# Adapters.net
KiCad netlist of a schematic drawn in Altium Designer
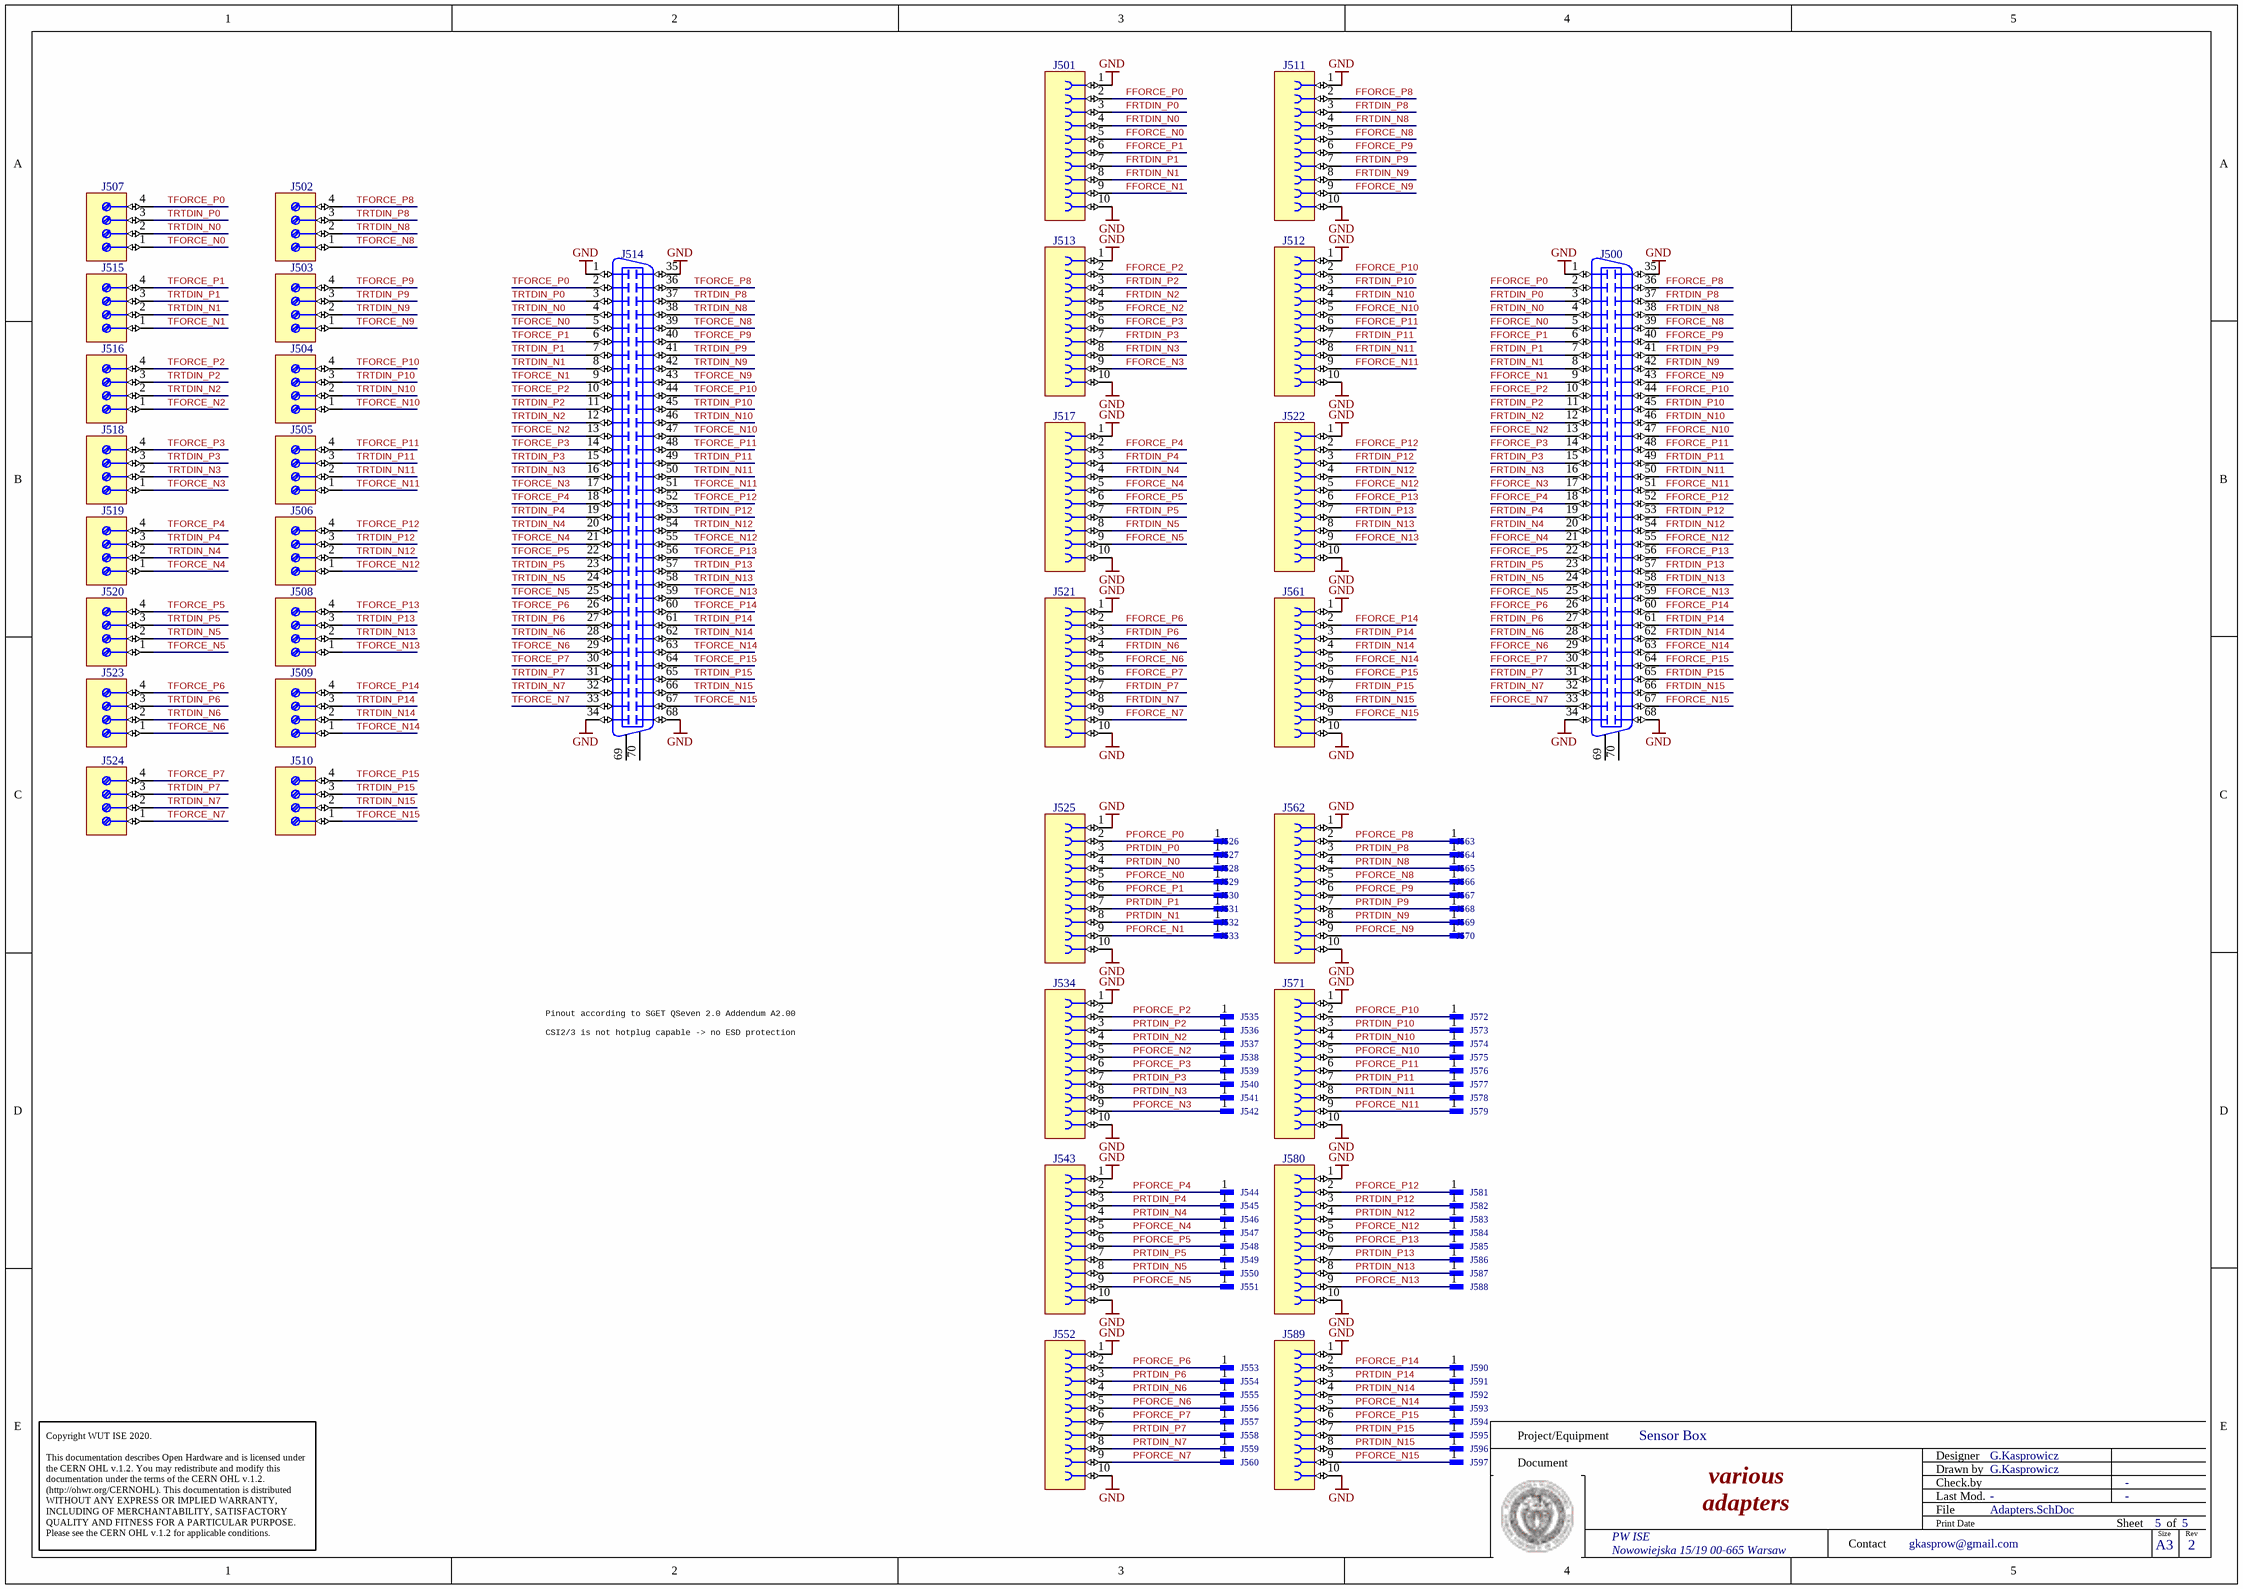
[diagram p0: Adapters.SchDoc]

(export (version "E")
  (design (tool "Eeschema 10.0.6"))
  (components
    (comp (ref "J500")
      (value "DNP")
      (footprint "MOLEX_71430-0013")
      (description "Very High Density Cable Interconnect (VHDCI ) 68 Female")
      (fields
        (field (name "PART NUMBER") "MOLEX_71430-0013")
        (field (name "MANUFACTURER") "MOLEX")
        (field (name "AUTHOR") "CERN DEM JLC")
      )
      (libsource (lib "FMC_DIO_32ch_lvds_a") (part "MOLEX_71430-0013"))
    )
    (comp (ref "J501")
      (value "FFC/FPC")
      (footprint "MOLEX_52745-1097")
      (description "Connector 10 Female")
      (fields
        (field (name "PART NUMBER") "MOLEX_52745-1097")
        (field (name "MANUFACTURER") "MOLEX")
        (field (name "AUTHOR") "CERN DEM JLC")
      )
      (libsource (lib "Connectors") (part "Connector 10 Female"))
    )
    (comp (ref "J502")
      (value "~")
      (footprint "PHOENIX_1725672")
      (description "Terminal Block, 4 Positions, Screw Connection")
      (fields
        (field (name "PART NUMBER") "PHOENIX_1725672")
        (field (name "MANUFACTURER") "PHOENIX CONTACT")
        (field (name "AUTHOR") "CERN DEM JMW")
      )
      (libsource (lib "Connectors") (part "Terminal Block_4 Positions_Screw Connection"))
    )
    (comp (ref "J503")
      (value "~")
      (footprint "PHOENIX_1725672")
      (description "Terminal Block, 4 Positions, Screw Connection")
      (fields
        (field (name "PART NUMBER") "PHOENIX_1725672")
        (field (name "MANUFACTURER") "PHOENIX CONTACT")
        (field (name "AUTHOR") "CERN DEM JMW")
      )
      (libsource (lib "Connectors") (part "Terminal Block_4 Positions_Screw Connection"))
    )
    (comp (ref "J504")
      (value "~")
      (footprint "PHOENIX_1725672")
      (description "Terminal Block, 4 Positions, Screw Connection")
      (fields
        (field (name "PART NUMBER") "PHOENIX_1725672")
        (field (name "MANUFACTURER") "PHOENIX CONTACT")
        (field (name "AUTHOR") "CERN DEM JMW")
      )
      (libsource (lib "Connectors") (part "Terminal Block_4 Positions_Screw Connection"))
    )
    (comp (ref "J505")
      (value "~")
      (footprint "PHOENIX_1725672")
      (description "Terminal Block, 4 Positions, Screw Connection")
      (fields
        (field (name "PART NUMBER") "PHOENIX_1725672")
        (field (name "MANUFACTURER") "PHOENIX CONTACT")
        (field (name "AUTHOR") "CERN DEM JMW")
      )
      (libsource (lib "Connectors") (part "Terminal Block_4 Positions_Screw Connection"))
    )
    (comp (ref "J506")
      (value "~")
      (footprint "PHOENIX_1725672")
      (description "Terminal Block, 4 Positions, Screw Connection")
      (fields
        (field (name "PART NUMBER") "PHOENIX_1725672")
        (field (name "MANUFACTURER") "PHOENIX CONTACT")
        (field (name "AUTHOR") "CERN DEM JMW")
      )
      (libsource (lib "Connectors") (part "Terminal Block_4 Positions_Screw Connection"))
    )
    (comp (ref "J507")
      (value "~")
      (footprint "PHOENIX_1725672")
      (description "Terminal Block, 4 Positions, Screw Connection")
      (fields
        (field (name "PART NUMBER") "PHOENIX_1725672")
        (field (name "MANUFACTURER") "PHOENIX CONTACT")
        (field (name "AUTHOR") "CERN DEM JMW")
      )
      (libsource (lib "Connectors") (part "Terminal Block_4 Positions_Screw Connection"))
    )
    (comp (ref "J508")
      (value "~")
      (footprint "PHOENIX_1725672")
      (description "Terminal Block, 4 Positions, Screw Connection")
      (fields
        (field (name "PART NUMBER") "PHOENIX_1725672")
        (field (name "MANUFACTURER") "PHOENIX CONTACT")
        (field (name "AUTHOR") "CERN DEM JMW")
      )
      (libsource (lib "Connectors") (part "Terminal Block_4 Positions_Screw Connection"))
    )
    (comp (ref "J509")
      (value "~")
      (footprint "PHOENIX_1725672")
      (description "Terminal Block, 4 Positions, Screw Connection")
      (fields
        (field (name "PART NUMBER") "PHOENIX_1725672")
        (field (name "MANUFACTURER") "PHOENIX CONTACT")
        (field (name "AUTHOR") "CERN DEM JMW")
      )
      (libsource (lib "Connectors") (part "Terminal Block_4 Positions_Screw Connection"))
    )
    (comp (ref "J510")
      (value "~")
      (footprint "PHOENIX_1725672")
      (description "Terminal Block, 4 Positions, Screw Connection")
      (fields
        (field (name "PART NUMBER") "PHOENIX_1725672")
        (field (name "MANUFACTURER") "PHOENIX CONTACT")
        (field (name "AUTHOR") "CERN DEM JMW")
      )
      (libsource (lib "Connectors") (part "Terminal Block_4 Positions_Screw Connection"))
    )
    (comp (ref "J511")
      (value "FFC/FPC")
      (footprint "MOLEX_52745-1097")
      (description "Connector 10 Female")
      (fields
        (field (name "PART NUMBER") "MOLEX_52745-1097")
        (field (name "MANUFACTURER") "MOLEX")
        (field (name "AUTHOR") "CERN DEM JLC")
      )
      (libsource (lib "Connectors") (part "Connector 10 Female"))
    )
    (comp (ref "J512")
      (value "FFC/FPC")
      (footprint "MOLEX_52745-1097")
      (description "Connector 10 Female")
      (fields
        (field (name "PART NUMBER") "MOLEX_52745-1097")
        (field (name "MANUFACTURER") "MOLEX")
        (field (name "AUTHOR") "CERN DEM JLC")
      )
      (libsource (lib "Connectors") (part "Connector 10 Female"))
    )
    (comp (ref "J513")
      (value "FFC/FPC")
      (footprint "MOLEX_52745-1097")
      (description "Connector 10 Female")
      (fields
        (field (name "PART NUMBER") "MOLEX_52745-1097")
        (field (name "MANUFACTURER") "MOLEX")
        (field (name "AUTHOR") "CERN DEM JLC")
      )
      (libsource (lib "Connectors") (part "Connector 10 Female"))
    )
    (comp (ref "J514")
      (value "DNP")
      (footprint "MOLEX_71430-0013")
      (description "Very High Density Cable Interconnect (VHDCI ) 68 Female")
      (fields
        (field (name "PART NUMBER") "MOLEX_71430-0013")
        (field (name "MANUFACTURER") "MOLEX")
        (field (name "AUTHOR") "CERN DEM JLC")
      )
      (libsource (lib "FMC_DIO_32ch_lvds_a") (part "MOLEX_71430-0013"))
    )
    (comp (ref "J515")
      (value "~")
      (footprint "PHOENIX_1725672")
      (description "Terminal Block, 4 Positions, Screw Connection")
      (fields
        (field (name "PART NUMBER") "PHOENIX_1725672")
        (field (name "MANUFACTURER") "PHOENIX CONTACT")
        (field (name "AUTHOR") "CERN DEM JMW")
      )
      (libsource (lib "Connectors") (part "Terminal Block_4 Positions_Screw Connection"))
    )
    (comp (ref "J516")
      (value "~")
      (footprint "PHOENIX_1725672")
      (description "Terminal Block, 4 Positions, Screw Connection")
      (fields
        (field (name "PART NUMBER") "PHOENIX_1725672")
        (field (name "MANUFACTURER") "PHOENIX CONTACT")
        (field (name "AUTHOR") "CERN DEM JMW")
      )
      (libsource (lib "Connectors") (part "Terminal Block_4 Positions_Screw Connection"))
    )
    (comp (ref "J517")
      (value "FFC/FPC")
      (footprint "MOLEX_52745-1097")
      (description "Connector 10 Female")
      (fields
        (field (name "PART NUMBER") "MOLEX_52745-1097")
        (field (name "MANUFACTURER") "MOLEX")
        (field (name "AUTHOR") "CERN DEM JLC")
      )
      (libsource (lib "Connectors") (part "Connector 10 Female"))
    )
    (comp (ref "J518")
      (value "~")
      (footprint "PHOENIX_1725672")
      (description "Terminal Block, 4 Positions, Screw Connection")
      (fields
        (field (name "PART NUMBER") "PHOENIX_1725672")
        (field (name "MANUFACTURER") "PHOENIX CONTACT")
        (field (name "AUTHOR") "CERN DEM JMW")
      )
      (libsource (lib "Connectors") (part "Terminal Block_4 Positions_Screw Connection"))
    )
    (comp (ref "J519")
      (value "~")
      (footprint "PHOENIX_1725672")
      (description "Terminal Block, 4 Positions, Screw Connection")
      (fields
        (field (name "PART NUMBER") "PHOENIX_1725672")
        (field (name "MANUFACTURER") "PHOENIX CONTACT")
        (field (name "AUTHOR") "CERN DEM JMW")
      )
      (libsource (lib "Connectors") (part "Terminal Block_4 Positions_Screw Connection"))
    )
    (comp (ref "J520")
      (value "~")
      (footprint "PHOENIX_1725672")
      (description "Terminal Block, 4 Positions, Screw Connection")
      (fields
        (field (name "PART NUMBER") "PHOENIX_1725672")
        (field (name "MANUFACTURER") "PHOENIX CONTACT")
        (field (name "AUTHOR") "CERN DEM JMW")
      )
      (libsource (lib "Connectors") (part "Terminal Block_4 Positions_Screw Connection"))
    )
    (comp (ref "J521")
      (value "FFC/FPC")
      (footprint "MOLEX_52745-1097")
      (description "Connector 10 Female")
      (fields
        (field (name "PART NUMBER") "MOLEX_52745-1097")
        (field (name "MANUFACTURER") "MOLEX")
        (field (name "AUTHOR") "CERN DEM JLC")
      )
      (libsource (lib "Connectors") (part "Connector 10 Female"))
    )
    (comp (ref "J522")
      (value "FFC/FPC")
      (footprint "MOLEX_52745-1097")
      (description "Connector 10 Female")
      (fields
        (field (name "PART NUMBER") "MOLEX_52745-1097")
        (field (name "MANUFACTURER") "MOLEX")
        (field (name "AUTHOR") "CERN DEM JLC")
      )
      (libsource (lib "Connectors") (part "Connector 10 Female"))
    )
    (comp (ref "J523")
      (value "~")
      (footprint "PHOENIX_1725672")
      (description "Terminal Block, 4 Positions, Screw Connection")
      (fields
        (field (name "PART NUMBER") "PHOENIX_1725672")
        (field (name "MANUFACTURER") "PHOENIX CONTACT")
        (field (name "AUTHOR") "CERN DEM JMW")
      )
      (libsource (lib "Connectors") (part "Terminal Block_4 Positions_Screw Connection"))
    )
    (comp (ref "J524")
      (value "~")
      (footprint "PHOENIX_1725672")
      (description "Terminal Block, 4 Positions, Screw Connection")
      (fields
        (field (name "PART NUMBER") "PHOENIX_1725672")
        (field (name "MANUFACTURER") "PHOENIX CONTACT")
        (field (name "AUTHOR") "CERN DEM JMW")
      )
      (libsource (lib "Connectors") (part "Terminal Block_4 Positions_Screw Connection"))
    )
    (comp (ref "J525")
      (value "FFC/FPC")
      (footprint "MOLEX_52745-1097")
      (description "Connector 10 Female")
      (fields
        (field (name "PART NUMBER") "MOLEX_52745-1097")
        (field (name "MANUFACTURER") "MOLEX")
        (field (name "AUTHOR") "CERN DEM JLC")
      )
      (libsource (lib "Connectors") (part "Connector 10 Female"))
    )
    (comp (ref "J526")
      (value "SMD Pad")
      (footprint "R350X200")
      (description "Single SMD Pad")
      (fields (field (name "PART NUMBER") "SMD_PAD_3.5X2MM") (field (name "AUTHOR") "CERN DEM JLC"))
      (libsource (lib "Eletro-mechanical") (part "Single SMD Pad"))
    )
    (comp (ref "J527")
      (value "SMD Pad")
      (footprint "R350X200")
      (description "Single SMD Pad")
      (fields (field (name "PART NUMBER") "SMD_PAD_3.5X2MM") (field (name "AUTHOR") "CERN DEM JLC"))
      (libsource (lib "Eletro-mechanical") (part "Single SMD Pad"))
    )
    (comp (ref "J528")
      (value "SMD Pad")
      (footprint "R350X200")
      (description "Single SMD Pad")
      (fields (field (name "PART NUMBER") "SMD_PAD_3.5X2MM") (field (name "AUTHOR") "CERN DEM JLC"))
      (libsource (lib "Eletro-mechanical") (part "Single SMD Pad"))
    )
    (comp (ref "J529")
      (value "SMD Pad")
      (footprint "R350X200")
      (description "Single SMD Pad")
      (fields (field (name "PART NUMBER") "SMD_PAD_3.5X2MM") (field (name "AUTHOR") "CERN DEM JLC"))
      (libsource (lib "Eletro-mechanical") (part "Single SMD Pad"))
    )
    (comp (ref "J530")
      (value "SMD Pad")
      (footprint "R350X200")
      (description "Single SMD Pad")
      (fields (field (name "PART NUMBER") "SMD_PAD_3.5X2MM") (field (name "AUTHOR") "CERN DEM JLC"))
      (libsource (lib "Eletro-mechanical") (part "Single SMD Pad"))
    )
    (comp (ref "J531")
      (value "SMD Pad")
      (footprint "R350X200")
      (description "Single SMD Pad")
      (fields (field (name "PART NUMBER") "SMD_PAD_3.5X2MM") (field (name "AUTHOR") "CERN DEM JLC"))
      (libsource (lib "Eletro-mechanical") (part "Single SMD Pad"))
    )
    (comp (ref "J532")
      (value "SMD Pad")
      (footprint "R350X200")
      (description "Single SMD Pad")
      (fields (field (name "PART NUMBER") "SMD_PAD_3.5X2MM") (field (name "AUTHOR") "CERN DEM JLC"))
      (libsource (lib "Eletro-mechanical") (part "Single SMD Pad"))
    )
    (comp (ref "J533")
      (value "SMD Pad")
      (footprint "R350X200")
      (description "Single SMD Pad")
      (fields (field (name "PART NUMBER") "SMD_PAD_3.5X2MM") (field (name "AUTHOR") "CERN DEM JLC"))
      (libsource (lib "Eletro-mechanical") (part "Single SMD Pad"))
    )
    (comp (ref "J534")
      (value "FFC/FPC")
      (footprint "MOLEX_52745-1097")
      (description "Connector 10 Female")
      (fields
        (field (name "PART NUMBER") "MOLEX_52745-1097")
        (field (name "MANUFACTURER") "MOLEX")
        (field (name "AUTHOR") "CERN DEM JLC")
      )
      (libsource (lib "Connectors") (part "Connector 10 Female"))
    )
    (comp (ref "J535")
      (value "SMD Pad")
      (footprint "R350X200")
      (description "Single SMD Pad")
      (fields (field (name "PART NUMBER") "SMD_PAD_3.5X2MM") (field (name "AUTHOR") "CERN DEM JLC"))
      (libsource (lib "Eletro-mechanical") (part "Single SMD Pad"))
    )
    (comp (ref "J536")
      (value "SMD Pad")
      (footprint "R350X200")
      (description "Single SMD Pad")
      (fields (field (name "PART NUMBER") "SMD_PAD_3.5X2MM") (field (name "AUTHOR") "CERN DEM JLC"))
      (libsource (lib "Eletro-mechanical") (part "Single SMD Pad"))
    )
    (comp (ref "J537")
      (value "SMD Pad")
      (footprint "R350X200")
      (description "Single SMD Pad")
      (fields (field (name "PART NUMBER") "SMD_PAD_3.5X2MM") (field (name "AUTHOR") "CERN DEM JLC"))
      (libsource (lib "Eletro-mechanical") (part "Single SMD Pad"))
    )
    (comp (ref "J538")
      (value "SMD Pad")
      (footprint "R350X200")
      (description "Single SMD Pad")
      (fields (field (name "PART NUMBER") "SMD_PAD_3.5X2MM") (field (name "AUTHOR") "CERN DEM JLC"))
      (libsource (lib "Eletro-mechanical") (part "Single SMD Pad"))
    )
    (comp (ref "J539")
      (value "SMD Pad")
      (footprint "R350X200")
      (description "Single SMD Pad")
      (fields (field (name "PART NUMBER") "SMD_PAD_3.5X2MM") (field (name "AUTHOR") "CERN DEM JLC"))
      (libsource (lib "Eletro-mechanical") (part "Single SMD Pad"))
    )
    (comp (ref "J540")
      (value "SMD Pad")
      (footprint "R350X200")
      (description "Single SMD Pad")
      (fields (field (name "PART NUMBER") "SMD_PAD_3.5X2MM") (field (name "AUTHOR") "CERN DEM JLC"))
      (libsource (lib "Eletro-mechanical") (part "Single SMD Pad"))
    )
    (comp (ref "J541")
      (value "SMD Pad")
      (footprint "R350X200")
      (description "Single SMD Pad")
      (fields (field (name "PART NUMBER") "SMD_PAD_3.5X2MM") (field (name "AUTHOR") "CERN DEM JLC"))
      (libsource (lib "Eletro-mechanical") (part "Single SMD Pad"))
    )
    (comp (ref "J542")
      (value "SMD Pad")
      (footprint "R350X200")
      (description "Single SMD Pad")
      (fields (field (name "PART NUMBER") "SMD_PAD_3.5X2MM") (field (name "AUTHOR") "CERN DEM JLC"))
      (libsource (lib "Eletro-mechanical") (part "Single SMD Pad"))
    )
    (comp (ref "J543")
      (value "FFC/FPC")
      (footprint "MOLEX_52745-1097")
      (description "Connector 10 Female")
      (fields
        (field (name "PART NUMBER") "MOLEX_52745-1097")
        (field (name "MANUFACTURER") "MOLEX")
        (field (name "AUTHOR") "CERN DEM JLC")
      )
      (libsource (lib "Connectors") (part "Connector 10 Female"))
    )
    (comp (ref "J544")
      (value "SMD Pad")
      (footprint "R350X200")
      (description "Single SMD Pad")
      (fields (field (name "PART NUMBER") "SMD_PAD_3.5X2MM") (field (name "AUTHOR") "CERN DEM JLC"))
      (libsource (lib "Eletro-mechanical") (part "Single SMD Pad"))
    )
    (comp (ref "J545")
      (value "SMD Pad")
      (footprint "R350X200")
      (description "Single SMD Pad")
      (fields (field (name "PART NUMBER") "SMD_PAD_3.5X2MM") (field (name "AUTHOR") "CERN DEM JLC"))
      (libsource (lib "Eletro-mechanical") (part "Single SMD Pad"))
    )
    (comp (ref "J546")
      (value "SMD Pad")
      (footprint "R350X200")
      (description "Single SMD Pad")
      (fields (field (name "PART NUMBER") "SMD_PAD_3.5X2MM") (field (name "AUTHOR") "CERN DEM JLC"))
      (libsource (lib "Eletro-mechanical") (part "Single SMD Pad"))
    )
    (comp (ref "J547")
      (value "SMD Pad")
      (footprint "R350X200")
      (description "Single SMD Pad")
      (fields (field (name "PART NUMBER") "SMD_PAD_3.5X2MM") (field (name "AUTHOR") "CERN DEM JLC"))
      (libsource (lib "Eletro-mechanical") (part "Single SMD Pad"))
    )
    (comp (ref "J548")
      (value "SMD Pad")
      (footprint "R350X200")
      (description "Single SMD Pad")
      (fields (field (name "PART NUMBER") "SMD_PAD_3.5X2MM") (field (name "AUTHOR") "CERN DEM JLC"))
      (libsource (lib "Eletro-mechanical") (part "Single SMD Pad"))
    )
    (comp (ref "J549")
      (value "SMD Pad")
      (footprint "R350X200")
      (description "Single SMD Pad")
      (fields (field (name "PART NUMBER") "SMD_PAD_3.5X2MM") (field (name "AUTHOR") "CERN DEM JLC"))
      (libsource (lib "Eletro-mechanical") (part "Single SMD Pad"))
    )
    (comp (ref "J550")
      (value "SMD Pad")
      (footprint "R350X200")
      (description "Single SMD Pad")
      (fields (field (name "PART NUMBER") "SMD_PAD_3.5X2MM") (field (name "AUTHOR") "CERN DEM JLC"))
      (libsource (lib "Eletro-mechanical") (part "Single SMD Pad"))
    )
    (comp (ref "J551")
      (value "SMD Pad")
      (footprint "R350X200")
      (description "Single SMD Pad")
      (fields (field (name "PART NUMBER") "SMD_PAD_3.5X2MM") (field (name "AUTHOR") "CERN DEM JLC"))
      (libsource (lib "Eletro-mechanical") (part "Single SMD Pad"))
    )
    (comp (ref "J552")
      (value "FFC/FPC")
      (footprint "MOLEX_52745-1097")
      (description "Connector 10 Female")
      (fields
        (field (name "PART NUMBER") "MOLEX_52745-1097")
        (field (name "MANUFACTURER") "MOLEX")
        (field (name "AUTHOR") "CERN DEM JLC")
      )
      (libsource (lib "Connectors") (part "Connector 10 Female"))
    )
    (comp (ref "J553")
      (value "SMD Pad")
      (footprint "R350X200")
      (description "Single SMD Pad")
      (fields (field (name "PART NUMBER") "SMD_PAD_3.5X2MM") (field (name "AUTHOR") "CERN DEM JLC"))
      (libsource (lib "Eletro-mechanical") (part "Single SMD Pad"))
    )
    (comp (ref "J554")
      (value "SMD Pad")
      (footprint "R350X200")
      (description "Single SMD Pad")
      (fields (field (name "PART NUMBER") "SMD_PAD_3.5X2MM") (field (name "AUTHOR") "CERN DEM JLC"))
      (libsource (lib "Eletro-mechanical") (part "Single SMD Pad"))
    )
    (comp (ref "J555")
      (value "SMD Pad")
      (footprint "R350X200")
      (description "Single SMD Pad")
      (fields (field (name "PART NUMBER") "SMD_PAD_3.5X2MM") (field (name "AUTHOR") "CERN DEM JLC"))
      (libsource (lib "Eletro-mechanical") (part "Single SMD Pad"))
    )
    (comp (ref "J556")
      (value "SMD Pad")
      (footprint "R350X200")
      (description "Single SMD Pad")
      (fields (field (name "PART NUMBER") "SMD_PAD_3.5X2MM") (field (name "AUTHOR") "CERN DEM JLC"))
      (libsource (lib "Eletro-mechanical") (part "Single SMD Pad"))
    )
    (comp (ref "J557")
      (value "SMD Pad")
      (footprint "R350X200")
      (description "Single SMD Pad")
      (fields (field (name "PART NUMBER") "SMD_PAD_3.5X2MM") (field (name "AUTHOR") "CERN DEM JLC"))
      (libsource (lib "Eletro-mechanical") (part "Single SMD Pad"))
    )
    (comp (ref "J558")
      (value "SMD Pad")
      (footprint "R350X200")
      (description "Single SMD Pad")
      (fields (field (name "PART NUMBER") "SMD_PAD_3.5X2MM") (field (name "AUTHOR") "CERN DEM JLC"))
      (libsource (lib "Eletro-mechanical") (part "Single SMD Pad"))
    )
    (comp (ref "J559")
      (value "SMD Pad")
      (footprint "R350X200")
      (description "Single SMD Pad")
      (fields (field (name "PART NUMBER") "SMD_PAD_3.5X2MM") (field (name "AUTHOR") "CERN DEM JLC"))
      (libsource (lib "Eletro-mechanical") (part "Single SMD Pad"))
    )
    (comp (ref "J560")
      (value "SMD Pad")
      (footprint "R350X200")
      (description "Single SMD Pad")
      (fields (field (name "PART NUMBER") "SMD_PAD_3.5X2MM") (field (name "AUTHOR") "CERN DEM JLC"))
      (libsource (lib "Eletro-mechanical") (part "Single SMD Pad"))
    )
    (comp (ref "J561")
      (value "FFC/FPC")
      (footprint "MOLEX_52745-1097")
      (description "Connector 10 Female")
      (fields
        (field (name "PART NUMBER") "MOLEX_52745-1097")
        (field (name "MANUFACTURER") "MOLEX")
        (field (name "AUTHOR") "CERN DEM JLC")
      )
      (libsource (lib "Connectors") (part "Connector 10 Female"))
    )
    (comp (ref "J562")
      (value "FFC/FPC")
      (footprint "MOLEX_52745-1097")
      (description "Connector 10 Female")
      (fields
        (field (name "PART NUMBER") "MOLEX_52745-1097")
        (field (name "MANUFACTURER") "MOLEX")
        (field (name "AUTHOR") "CERN DEM JLC")
      )
      (libsource (lib "Connectors") (part "Connector 10 Female"))
    )
    (comp (ref "J563")
      (value "SMD Pad")
      (footprint "R350X200")
      (description "Single SMD Pad")
      (fields (field (name "PART NUMBER") "SMD_PAD_3.5X2MM") (field (name "AUTHOR") "CERN DEM JLC"))
      (libsource (lib "Eletro-mechanical") (part "Single SMD Pad"))
    )
    (comp (ref "J564")
      (value "SMD Pad")
      (footprint "R350X200")
      (description "Single SMD Pad")
      (fields (field (name "PART NUMBER") "SMD_PAD_3.5X2MM") (field (name "AUTHOR") "CERN DEM JLC"))
      (libsource (lib "Eletro-mechanical") (part "Single SMD Pad"))
    )
    (comp (ref "J565")
      (value "SMD Pad")
      (footprint "R350X200")
      (description "Single SMD Pad")
      (fields (field (name "PART NUMBER") "SMD_PAD_3.5X2MM") (field (name "AUTHOR") "CERN DEM JLC"))
      (libsource (lib "Eletro-mechanical") (part "Single SMD Pad"))
    )
    (comp (ref "J566")
      (value "SMD Pad")
      (footprint "R350X200")
      (description "Single SMD Pad")
      (fields (field (name "PART NUMBER") "SMD_PAD_3.5X2MM") (field (name "AUTHOR") "CERN DEM JLC"))
      (libsource (lib "Eletro-mechanical") (part "Single SMD Pad"))
    )
    (comp (ref "J567")
      (value "SMD Pad")
      (footprint "R350X200")
      (description "Single SMD Pad")
      (fields (field (name "PART NUMBER") "SMD_PAD_3.5X2MM") (field (name "AUTHOR") "CERN DEM JLC"))
      (libsource (lib "Eletro-mechanical") (part "Single SMD Pad"))
    )
    (comp (ref "J568")
      (value "SMD Pad")
      (footprint "R350X200")
      (description "Single SMD Pad")
      (fields (field (name "PART NUMBER") "SMD_PAD_3.5X2MM") (field (name "AUTHOR") "CERN DEM JLC"))
      (libsource (lib "Eletro-mechanical") (part "Single SMD Pad"))
    )
    (comp (ref "J569")
      (value "SMD Pad")
      (footprint "R350X200")
      (description "Single SMD Pad")
      (fields (field (name "PART NUMBER") "SMD_PAD_3.5X2MM") (field (name "AUTHOR") "CERN DEM JLC"))
      (libsource (lib "Eletro-mechanical") (part "Single SMD Pad"))
    )
    (comp (ref "J570")
      (value "SMD Pad")
      (footprint "R350X200")
      (description "Single SMD Pad")
      (fields (field (name "PART NUMBER") "SMD_PAD_3.5X2MM") (field (name "AUTHOR") "CERN DEM JLC"))
      (libsource (lib "Eletro-mechanical") (part "Single SMD Pad"))
    )
    (comp (ref "J571")
      (value "FFC/FPC")
      (footprint "MOLEX_52745-1097")
      (description "Connector 10 Female")
      (fields
        (field (name "PART NUMBER") "MOLEX_52745-1097")
        (field (name "MANUFACTURER") "MOLEX")
        (field (name "AUTHOR") "CERN DEM JLC")
      )
      (libsource (lib "Connectors") (part "Connector 10 Female"))
    )
    (comp (ref "J572")
      (value "SMD Pad")
      (footprint "R350X200")
      (description "Single SMD Pad")
      (fields (field (name "PART NUMBER") "SMD_PAD_3.5X2MM") (field (name "AUTHOR") "CERN DEM JLC"))
      (libsource (lib "Eletro-mechanical") (part "Single SMD Pad"))
    )
    (comp (ref "J573")
      (value "SMD Pad")
      (footprint "R350X200")
      (description "Single SMD Pad")
      (fields (field (name "PART NUMBER") "SMD_PAD_3.5X2MM") (field (name "AUTHOR") "CERN DEM JLC"))
      (libsource (lib "Eletro-mechanical") (part "Single SMD Pad"))
    )
    (comp (ref "J574")
      (value "SMD Pad")
      (footprint "R350X200")
      (description "Single SMD Pad")
      (fields (field (name "PART NUMBER") "SMD_PAD_3.5X2MM") (field (name "AUTHOR") "CERN DEM JLC"))
      (libsource (lib "Eletro-mechanical") (part "Single SMD Pad"))
    )
    (comp (ref "J575")
      (value "SMD Pad")
      (footprint "R350X200")
      (description "Single SMD Pad")
      (fields (field (name "PART NUMBER") "SMD_PAD_3.5X2MM") (field (name "AUTHOR") "CERN DEM JLC"))
      (libsource (lib "Eletro-mechanical") (part "Single SMD Pad"))
    )
    (comp (ref "J576")
      (value "SMD Pad")
      (footprint "R350X200")
      (description "Single SMD Pad")
      (fields (field (name "PART NUMBER") "SMD_PAD_3.5X2MM") (field (name "AUTHOR") "CERN DEM JLC"))
      (libsource (lib "Eletro-mechanical") (part "Single SMD Pad"))
    )
    (comp (ref "J577")
      (value "SMD Pad")
      (footprint "R350X200")
      (description "Single SMD Pad")
      (fields (field (name "PART NUMBER") "SMD_PAD_3.5X2MM") (field (name "AUTHOR") "CERN DEM JLC"))
      (libsource (lib "Eletro-mechanical") (part "Single SMD Pad"))
    )
    (comp (ref "J578")
      (value "SMD Pad")
      (footprint "R350X200")
      (description "Single SMD Pad")
      (fields (field (name "PART NUMBER") "SMD_PAD_3.5X2MM") (field (name "AUTHOR") "CERN DEM JLC"))
      (libsource (lib "Eletro-mechanical") (part "Single SMD Pad"))
    )
    (comp (ref "J579")
      (value "SMD Pad")
      (footprint "R350X200")
      (description "Single SMD Pad")
      (fields (field (name "PART NUMBER") "SMD_PAD_3.5X2MM") (field (name "AUTHOR") "CERN DEM JLC"))
      (libsource (lib "Eletro-mechanical") (part "Single SMD Pad"))
    )
    (comp (ref "J580")
      (value "FFC/FPC")
      (footprint "MOLEX_52745-1097")
      (description "Connector 10 Female")
      (fields
        (field (name "PART NUMBER") "MOLEX_52745-1097")
        (field (name "MANUFACTURER") "MOLEX")
        (field (name "AUTHOR") "CERN DEM JLC")
      )
      (libsource (lib "Connectors") (part "Connector 10 Female"))
    )
    (comp (ref "J581")
      (value "SMD Pad")
      (footprint "R350X200")
      (description "Single SMD Pad")
      (fields (field (name "PART NUMBER") "SMD_PAD_3.5X2MM") (field (name "AUTHOR") "CERN DEM JLC"))
      (libsource (lib "Eletro-mechanical") (part "Single SMD Pad"))
    )
    (comp (ref "J582")
      (value "SMD Pad")
      (footprint "R350X200")
      (description "Single SMD Pad")
      (fields (field (name "PART NUMBER") "SMD_PAD_3.5X2MM") (field (name "AUTHOR") "CERN DEM JLC"))
      (libsource (lib "Eletro-mechanical") (part "Single SMD Pad"))
    )
    (comp (ref "J583")
      (value "SMD Pad")
      (footprint "R350X200")
      (description "Single SMD Pad")
      (fields (field (name "PART NUMBER") "SMD_PAD_3.5X2MM") (field (name "AUTHOR") "CERN DEM JLC"))
      (libsource (lib "Eletro-mechanical") (part "Single SMD Pad"))
    )
    (comp (ref "J584")
      (value "SMD Pad")
      (footprint "R350X200")
      (description "Single SMD Pad")
      (fields (field (name "PART NUMBER") "SMD_PAD_3.5X2MM") (field (name "AUTHOR") "CERN DEM JLC"))
      (libsource (lib "Eletro-mechanical") (part "Single SMD Pad"))
    )
    (comp (ref "J585")
      (value "SMD Pad")
      (footprint "R350X200")
      (description "Single SMD Pad")
      (fields (field (name "PART NUMBER") "SMD_PAD_3.5X2MM") (field (name "AUTHOR") "CERN DEM JLC"))
      (libsource (lib "Eletro-mechanical") (part "Single SMD Pad"))
    )
    (comp (ref "J586")
      (value "SMD Pad")
      (footprint "R350X200")
      (description "Single SMD Pad")
      (fields (field (name "PART NUMBER") "SMD_PAD_3.5X2MM") (field (name "AUTHOR") "CERN DEM JLC"))
      (libsource (lib "Eletro-mechanical") (part "Single SMD Pad"))
    )
    (comp (ref "J587")
      (value "SMD Pad")
      (footprint "R350X200")
      (description "Single SMD Pad")
      (fields (field (name "PART NUMBER") "SMD_PAD_3.5X2MM") (field (name "AUTHOR") "CERN DEM JLC"))
      (libsource (lib "Eletro-mechanical") (part "Single SMD Pad"))
    )
    (comp (ref "J588")
      (value "SMD Pad")
      (footprint "R350X200")
      (description "Single SMD Pad")
      (fields (field (name "PART NUMBER") "SMD_PAD_3.5X2MM") (field (name "AUTHOR") "CERN DEM JLC"))
      (libsource (lib "Eletro-mechanical") (part "Single SMD Pad"))
    )
    (comp (ref "J589")
      (value "FFC/FPC")
      (footprint "MOLEX_52745-1097")
      (description "Connector 10 Female")
      (fields
        (field (name "PART NUMBER") "MOLEX_52745-1097")
        (field (name "MANUFACTURER") "MOLEX")
        (field (name "AUTHOR") "CERN DEM JLC")
      )
      (libsource (lib "Connectors") (part "Connector 10 Female"))
    )
    (comp (ref "J590")
      (value "SMD Pad")
      (footprint "R350X200")
      (description "Single SMD Pad")
      (fields (field (name "PART NUMBER") "SMD_PAD_3.5X2MM") (field (name "AUTHOR") "CERN DEM JLC"))
      (libsource (lib "Eletro-mechanical") (part "Single SMD Pad"))
    )
    (comp (ref "J591")
      (value "SMD Pad")
      (footprint "R350X200")
      (description "Single SMD Pad")
      (fields (field (name "PART NUMBER") "SMD_PAD_3.5X2MM") (field (name "AUTHOR") "CERN DEM JLC"))
      (libsource (lib "Eletro-mechanical") (part "Single SMD Pad"))
    )
    (comp (ref "J592")
      (value "SMD Pad")
      (footprint "R350X200")
      (description "Single SMD Pad")
      (fields (field (name "PART NUMBER") "SMD_PAD_3.5X2MM") (field (name "AUTHOR") "CERN DEM JLC"))
      (libsource (lib "Eletro-mechanical") (part "Single SMD Pad"))
    )
    (comp (ref "J593")
      (value "SMD Pad")
      (footprint "R350X200")
      (description "Single SMD Pad")
      (fields (field (name "PART NUMBER") "SMD_PAD_3.5X2MM") (field (name "AUTHOR") "CERN DEM JLC"))
      (libsource (lib "Eletro-mechanical") (part "Single SMD Pad"))
    )
    (comp (ref "J594")
      (value "SMD Pad")
      (footprint "R350X200")
      (description "Single SMD Pad")
      (fields (field (name "PART NUMBER") "SMD_PAD_3.5X2MM") (field (name "AUTHOR") "CERN DEM JLC"))
      (libsource (lib "Eletro-mechanical") (part "Single SMD Pad"))
    )
    (comp (ref "J595")
      (value "SMD Pad")
      (footprint "R350X200")
      (description "Single SMD Pad")
      (fields (field (name "PART NUMBER") "SMD_PAD_3.5X2MM") (field (name "AUTHOR") "CERN DEM JLC"))
      (libsource (lib "Eletro-mechanical") (part "Single SMD Pad"))
    )
    (comp (ref "J596")
      (value "SMD Pad")
      (footprint "R350X200")
      (description "Single SMD Pad")
      (fields (field (name "PART NUMBER") "SMD_PAD_3.5X2MM") (field (name "AUTHOR") "CERN DEM JLC"))
      (libsource (lib "Eletro-mechanical") (part "Single SMD Pad"))
    )
    (comp (ref "J597")
      (value "SMD Pad")
      (footprint "R350X200")
      (description "Single SMD Pad")
      (fields (field (name "PART NUMBER") "SMD_PAD_3.5X2MM") (field (name "AUTHOR") "CERN DEM JLC"))
      (libsource (lib "Eletro-mechanical") (part "Single SMD Pad"))
    )
  )
  (nets
    (net (code "1") (name "/FFORCE_N0") (class "Default")
      (node (ref "J500") (pin "5") (pinfunction "5_5") (pintype "bidirectional"))
      (node (ref "J501") (pin "5") (pinfunction "5_5") (pintype "bidirectional"))
    )
    (net (code "2") (name "/FFORCE_N1") (class "Default")
      (node (ref "J500") (pin "9") (pinfunction "9_9") (pintype "bidirectional"))
      (node (ref "J501") (pin "9") (pinfunction "9_9") (pintype "bidirectional"))
    )
    (net (code "3") (name "/FFORCE_N2") (class "Default")
      (node (ref "J500") (pin "13") (pinfunction "13_13") (pintype "bidirectional"))
      (node (ref "J513") (pin "5") (pinfunction "5_5") (pintype "bidirectional"))
    )
    (net (code "4") (name "/FFORCE_N3") (class "Default")
      (node (ref "J500") (pin "17") (pinfunction "17_17") (pintype "bidirectional"))
      (node (ref "J513") (pin "9") (pinfunction "9_9") (pintype "bidirectional"))
    )
    (net (code "5") (name "/FFORCE_N4") (class "Default")
      (node (ref "J500") (pin "21") (pinfunction "21_21") (pintype "bidirectional"))
      (node (ref "J517") (pin "5") (pinfunction "5_5") (pintype "bidirectional"))
    )
    (net (code "6") (name "/FFORCE_N5") (class "Default")
      (node (ref "J500") (pin "25") (pinfunction "25_25") (pintype "bidirectional"))
      (node (ref "J517") (pin "9") (pinfunction "9_9") (pintype "bidirectional"))
    )
    (net (code "7") (name "/FFORCE_N6") (class "Default")
      (node (ref "J500") (pin "29") (pinfunction "29_29") (pintype "bidirectional"))
      (node (ref "J521") (pin "5") (pinfunction "5_5") (pintype "bidirectional"))
    )
    (net (code "8") (name "/FFORCE_N7") (class "Default")
      (node (ref "J500") (pin "33") (pinfunction "33_33") (pintype "bidirectional"))
      (node (ref "J521") (pin "9") (pinfunction "9_9") (pintype "bidirectional"))
    )
    (net (code "9") (name "/FFORCE_N8") (class "Default")
      (node (ref "J500") (pin "39") (pinfunction "39_39") (pintype "bidirectional"))
      (node (ref "J511") (pin "5") (pinfunction "5_5") (pintype "bidirectional"))
    )
    (net (code "10") (name "/FFORCE_N9") (class "Default")
      (node (ref "J500") (pin "43") (pinfunction "43_43") (pintype "bidirectional"))
      (node (ref "J511") (pin "9") (pinfunction "9_9") (pintype "bidirectional"))
    )
    (net (code "11") (name "/FFORCE_N10") (class "Default")
      (node (ref "J500") (pin "47") (pinfunction "47_47") (pintype "bidirectional"))
      (node (ref "J512") (pin "5") (pinfunction "5_5") (pintype "bidirectional"))
    )
    (net (code "12") (name "/FFORCE_N11") (class "Default")
      (node (ref "J500") (pin "51") (pinfunction "51_51") (pintype "bidirectional"))
      (node (ref "J512") (pin "9") (pinfunction "9_9") (pintype "bidirectional"))
    )
    (net (code "13") (name "/FFORCE_N12") (class "Default")
      (node (ref "J500") (pin "55") (pinfunction "55_55") (pintype "bidirectional"))
      (node (ref "J522") (pin "5") (pinfunction "5_5") (pintype "bidirectional"))
    )
    (net (code "14") (name "/FFORCE_N13") (class "Default")
      (node (ref "J500") (pin "59") (pinfunction "59_59") (pintype "bidirectional"))
      (node (ref "J522") (pin "9") (pinfunction "9_9") (pintype "bidirectional"))
    )
    (net (code "15") (name "/FFORCE_N14") (class "Default")
      (node (ref "J500") (pin "63") (pinfunction "63_63") (pintype "bidirectional"))
      (node (ref "J561") (pin "5") (pinfunction "5_5") (pintype "bidirectional"))
    )
    (net (code "16") (name "/FFORCE_N15") (class "Default")
      (node (ref "J500") (pin "67") (pinfunction "67_67") (pintype "bidirectional"))
      (node (ref "J561") (pin "9") (pinfunction "9_9") (pintype "bidirectional"))
    )
    (net (code "17") (name "/FFORCE_P0") (class "Default")
      (node (ref "J500") (pin "2") (pinfunction "2_2") (pintype "bidirectional"))
      (node (ref "J501") (pin "2") (pinfunction "2_2") (pintype "bidirectional"))
    )
    (net (code "18") (name "/FFORCE_P1") (class "Default")
      (node (ref "J500") (pin "6") (pinfunction "6_6") (pintype "bidirectional"))
      (node (ref "J501") (pin "6") (pinfunction "6_6") (pintype "bidirectional"))
    )
    (net (code "19") (name "/FFORCE_P2") (class "Default")
      (node (ref "J500") (pin "10") (pinfunction "10_10") (pintype "bidirectional"))
      (node (ref "J513") (pin "2") (pinfunction "2_2") (pintype "bidirectional"))
    )
    (net (code "20") (name "/FFORCE_P3") (class "Default")
      (node (ref "J500") (pin "14") (pinfunction "14_14") (pintype "bidirectional"))
      (node (ref "J513") (pin "6") (pinfunction "6_6") (pintype "bidirectional"))
    )
    (net (code "21") (name "/FFORCE_P4") (class "Default")
      (node (ref "J500") (pin "18") (pinfunction "18_18") (pintype "bidirectional"))
      (node (ref "J517") (pin "2") (pinfunction "2_2") (pintype "bidirectional"))
    )
    (net (code "22") (name "/FFORCE_P5") (class "Default")
      (node (ref "J500") (pin "22") (pinfunction "22_22") (pintype "bidirectional"))
      (node (ref "J517") (pin "6") (pinfunction "6_6") (pintype "bidirectional"))
    )
    (net (code "23") (name "/FFORCE_P6") (class "Default")
      (node (ref "J500") (pin "26") (pinfunction "26_26") (pintype "bidirectional"))
      (node (ref "J521") (pin "2") (pinfunction "2_2") (pintype "bidirectional"))
    )
    (net (code "24") (name "/FFORCE_P7") (class "Default")
      (node (ref "J500") (pin "30") (pinfunction "30_30") (pintype "bidirectional"))
      (node (ref "J521") (pin "6") (pinfunction "6_6") (pintype "bidirectional"))
    )
    (net (code "25") (name "/FFORCE_P8") (class "Default")
      (node (ref "J500") (pin "36") (pinfunction "36_36") (pintype "bidirectional"))
      (node (ref "J511") (pin "2") (pinfunction "2_2") (pintype "bidirectional"))
    )
    (net (code "26") (name "/FFORCE_P9") (class "Default")
      (node (ref "J500") (pin "40") (pinfunction "40_40") (pintype "bidirectional"))
      (node (ref "J511") (pin "6") (pinfunction "6_6") (pintype "bidirectional"))
    )
    (net (code "27") (name "/FFORCE_P10") (class "Default")
      (node (ref "J500") (pin "44") (pinfunction "44_44") (pintype "bidirectional"))
      (node (ref "J512") (pin "2") (pinfunction "2_2") (pintype "bidirectional"))
    )
    (net (code "28") (name "/FFORCE_P11") (class "Default")
      (node (ref "J500") (pin "48") (pinfunction "48_48") (pintype "bidirectional"))
      (node (ref "J512") (pin "6") (pinfunction "6_6") (pintype "bidirectional"))
    )
    (net (code "29") (name "/FFORCE_P12") (class "Default")
      (node (ref "J500") (pin "52") (pinfunction "52_52") (pintype "bidirectional"))
      (node (ref "J522") (pin "2") (pinfunction "2_2") (pintype "bidirectional"))
    )
    (net (code "30") (name "/FFORCE_P13") (class "Default")
      (node (ref "J500") (pin "56") (pinfunction "56_56") (pintype "bidirectional"))
      (node (ref "J522") (pin "6") (pinfunction "6_6") (pintype "bidirectional"))
    )
    (net (code "31") (name "/FFORCE_P14") (class "Default")
      (node (ref "J500") (pin "60") (pinfunction "60_60") (pintype "bidirectional"))
      (node (ref "J561") (pin "2") (pinfunction "2_2") (pintype "bidirectional"))
    )
    (net (code "32") (name "/FFORCE_P15") (class "Default")
      (node (ref "J500") (pin "64") (pinfunction "64_64") (pintype "bidirectional"))
      (node (ref "J561") (pin "6") (pinfunction "6_6") (pintype "bidirectional"))
    )
    (net (code "33") (name "/FRTDIN_N0") (class "Default")
      (node (ref "J500") (pin "4") (pinfunction "4_4") (pintype "bidirectional"))
      (node (ref "J501") (pin "4") (pinfunction "4_4") (pintype "bidirectional"))
    )
    (net (code "34") (name "/FRTDIN_N1") (class "Default")
      (node (ref "J500") (pin "8") (pinfunction "8_8") (pintype "bidirectional"))
      (node (ref "J501") (pin "8") (pinfunction "8_8") (pintype "bidirectional"))
    )
    (net (code "35") (name "/FRTDIN_N2") (class "Default")
      (node (ref "J500") (pin "12") (pinfunction "12_12") (pintype "bidirectional"))
      (node (ref "J513") (pin "4") (pinfunction "4_4") (pintype "bidirectional"))
    )
    (net (code "36") (name "/FRTDIN_N3") (class "Default")
      (node (ref "J500") (pin "16") (pinfunction "16_16") (pintype "bidirectional"))
      (node (ref "J513") (pin "8") (pinfunction "8_8") (pintype "bidirectional"))
    )
    (net (code "37") (name "/FRTDIN_N4") (class "Default")
      (node (ref "J500") (pin "20") (pinfunction "20_20") (pintype "bidirectional"))
      (node (ref "J517") (pin "4") (pinfunction "4_4") (pintype "bidirectional"))
    )
    (net (code "38") (name "/FRTDIN_N5") (class "Default")
      (node (ref "J500") (pin "24") (pinfunction "24_24") (pintype "bidirectional"))
      (node (ref "J517") (pin "8") (pinfunction "8_8") (pintype "bidirectional"))
    )
    (net (code "39") (name "/FRTDIN_N6") (class "Default")
      (node (ref "J500") (pin "28") (pinfunction "28_28") (pintype "bidirectional"))
      (node (ref "J521") (pin "4") (pinfunction "4_4") (pintype "bidirectional"))
    )
    (net (code "40") (name "/FRTDIN_N7") (class "Default")
      (node (ref "J500") (pin "32") (pinfunction "32_32") (pintype "bidirectional"))
      (node (ref "J521") (pin "8") (pinfunction "8_8") (pintype "bidirectional"))
    )
    (net (code "41") (name "/FRTDIN_N8") (class "Default")
      (node (ref "J500") (pin "38") (pinfunction "38_38") (pintype "bidirectional"))
      (node (ref "J511") (pin "4") (pinfunction "4_4") (pintype "bidirectional"))
    )
    (net (code "42") (name "/FRTDIN_N9") (class "Default")
      (node (ref "J500") (pin "42") (pinfunction "42_42") (pintype "bidirectional"))
      (node (ref "J511") (pin "8") (pinfunction "8_8") (pintype "bidirectional"))
    )
    (net (code "43") (name "/FRTDIN_N10") (class "Default")
      (node (ref "J500") (pin "46") (pinfunction "46_46") (pintype "bidirectional"))
      (node (ref "J512") (pin "4") (pinfunction "4_4") (pintype "bidirectional"))
    )
    (net (code "44") (name "/FRTDIN_N11") (class "Default")
      (node (ref "J500") (pin "50") (pinfunction "50_50") (pintype "bidirectional"))
      (node (ref "J512") (pin "8") (pinfunction "8_8") (pintype "bidirectional"))
    )
    (net (code "45") (name "/FRTDIN_N12") (class "Default")
      (node (ref "J500") (pin "54") (pinfunction "54_54") (pintype "bidirectional"))
      (node (ref "J522") (pin "4") (pinfunction "4_4") (pintype "bidirectional"))
    )
    (net (code "46") (name "/FRTDIN_N13") (class "Default")
      (node (ref "J500") (pin "58") (pinfunction "58_58") (pintype "bidirectional"))
      (node (ref "J522") (pin "8") (pinfunction "8_8") (pintype "bidirectional"))
    )
    (net (code "47") (name "/FRTDIN_N14") (class "Default")
      (node (ref "J500") (pin "62") (pinfunction "62_62") (pintype "bidirectional"))
      (node (ref "J561") (pin "4") (pinfunction "4_4") (pintype "bidirectional"))
    )
    (net (code "48") (name "/FRTDIN_N15") (class "Default")
      (node (ref "J500") (pin "66") (pinfunction "66_66") (pintype "bidirectional"))
      (node (ref "J561") (pin "8") (pinfunction "8_8") (pintype "bidirectional"))
    )
    (net (code "49") (name "/FRTDIN_P0") (class "Default")
      (node (ref "J500") (pin "3") (pinfunction "3_3") (pintype "bidirectional"))
      (node (ref "J501") (pin "3") (pinfunction "3_3") (pintype "bidirectional"))
    )
    (net (code "50") (name "/FRTDIN_P1") (class "Default")
      (node (ref "J500") (pin "7") (pinfunction "7_7") (pintype "bidirectional"))
      (node (ref "J501") (pin "7") (pinfunction "7_7") (pintype "bidirectional"))
    )
    (net (code "51") (name "/FRTDIN_P2") (class "Default")
      (node (ref "J500") (pin "11") (pinfunction "11_11") (pintype "bidirectional"))
      (node (ref "J513") (pin "3") (pinfunction "3_3") (pintype "bidirectional"))
    )
    (net (code "52") (name "/FRTDIN_P3") (class "Default")
      (node (ref "J500") (pin "15") (pinfunction "15_15") (pintype "bidirectional"))
      (node (ref "J513") (pin "7") (pinfunction "7_7") (pintype "bidirectional"))
    )
    (net (code "53") (name "/FRTDIN_P4") (class "Default")
      (node (ref "J500") (pin "19") (pinfunction "19_19") (pintype "bidirectional"))
      (node (ref "J517") (pin "3") (pinfunction "3_3") (pintype "bidirectional"))
    )
    (net (code "54") (name "/FRTDIN_P5") (class "Default")
      (node (ref "J500") (pin "23") (pinfunction "23_23") (pintype "bidirectional"))
      (node (ref "J517") (pin "7") (pinfunction "7_7") (pintype "bidirectional"))
    )
    (net (code "55") (name "/FRTDIN_P6") (class "Default")
      (node (ref "J500") (pin "27") (pinfunction "27_27") (pintype "bidirectional"))
      (node (ref "J521") (pin "3") (pinfunction "3_3") (pintype "bidirectional"))
    )
    (net (code "56") (name "/FRTDIN_P7") (class "Default")
      (node (ref "J500") (pin "31") (pinfunction "31_31") (pintype "bidirectional"))
      (node (ref "J521") (pin "7") (pinfunction "7_7") (pintype "bidirectional"))
    )
    (net (code "57") (name "/FRTDIN_P8") (class "Default")
      (node (ref "J500") (pin "37") (pinfunction "37_37") (pintype "bidirectional"))
      (node (ref "J511") (pin "3") (pinfunction "3_3") (pintype "bidirectional"))
    )
    (net (code "58") (name "/FRTDIN_P9") (class "Default")
      (node (ref "J500") (pin "41") (pinfunction "41_41") (pintype "bidirectional"))
      (node (ref "J511") (pin "7") (pinfunction "7_7") (pintype "bidirectional"))
    )
    (net (code "59") (name "/FRTDIN_P10") (class "Default")
      (node (ref "J500") (pin "45") (pinfunction "45_45") (pintype "bidirectional"))
      (node (ref "J512") (pin "3") (pinfunction "3_3") (pintype "bidirectional"))
    )
    (net (code "60") (name "/FRTDIN_P11") (class "Default")
      (node (ref "J500") (pin "49") (pinfunction "49_49") (pintype "bidirectional"))
      (node (ref "J512") (pin "7") (pinfunction "7_7") (pintype "bidirectional"))
    )
    (net (code "61") (name "/FRTDIN_P12") (class "Default")
      (node (ref "J500") (pin "53") (pinfunction "53_53") (pintype "bidirectional"))
      (node (ref "J522") (pin "3") (pinfunction "3_3") (pintype "bidirectional"))
    )
    (net (code "62") (name "/FRTDIN_P13") (class "Default")
      (node (ref "J500") (pin "57") (pinfunction "57_57") (pintype "bidirectional"))
      (node (ref "J522") (pin "7") (pinfunction "7_7") (pintype "bidirectional"))
    )
    (net (code "63") (name "/FRTDIN_P14") (class "Default")
      (node (ref "J500") (pin "61") (pinfunction "61_61") (pintype "bidirectional"))
      (node (ref "J561") (pin "3") (pinfunction "3_3") (pintype "bidirectional"))
    )
    (net (code "64") (name "/FRTDIN_P15") (class "Default")
      (node (ref "J500") (pin "65") (pinfunction "65_65") (pintype "bidirectional"))
      (node (ref "J561") (pin "7") (pinfunction "7_7") (pintype "bidirectional"))
    )
    (net (code "65") (name "/PFORCE_N0") (class "Default")
      (node (ref "J525") (pin "5") (pinfunction "5_5") (pintype "bidirectional"))
      (node (ref "J529") (pin "1") (pinfunction "1_1") (pintype "bidirectional"))
    )
    (net (code "66") (name "/PFORCE_N1") (class "Default")
      (node (ref "J525") (pin "9") (pinfunction "9_9") (pintype "bidirectional"))
      (node (ref "J533") (pin "1") (pinfunction "1_1") (pintype "bidirectional"))
    )
    (net (code "67") (name "/PFORCE_N2") (class "Default")
      (node (ref "J534") (pin "5") (pinfunction "5_5") (pintype "bidirectional"))
      (node (ref "J538") (pin "1") (pinfunction "1_1") (pintype "bidirectional"))
    )
    (net (code "68") (name "/PFORCE_N3") (class "Default")
      (node (ref "J534") (pin "9") (pinfunction "9_9") (pintype "bidirectional"))
      (node (ref "J542") (pin "1") (pinfunction "1_1") (pintype "bidirectional"))
    )
    (net (code "69") (name "/PFORCE_N4") (class "Default")
      (node (ref "J543") (pin "5") (pinfunction "5_5") (pintype "bidirectional"))
      (node (ref "J547") (pin "1") (pinfunction "1_1") (pintype "bidirectional"))
    )
    (net (code "70") (name "/PFORCE_N5") (class "Default")
      (node (ref "J543") (pin "9") (pinfunction "9_9") (pintype "bidirectional"))
      (node (ref "J551") (pin "1") (pinfunction "1_1") (pintype "bidirectional"))
    )
    (net (code "71") (name "/PFORCE_N6") (class "Default")
      (node (ref "J552") (pin "5") (pinfunction "5_5") (pintype "bidirectional"))
      (node (ref "J556") (pin "1") (pinfunction "1_1") (pintype "bidirectional"))
    )
    (net (code "72") (name "/PFORCE_N7") (class "Default")
      (node (ref "J552") (pin "9") (pinfunction "9_9") (pintype "bidirectional"))
      (node (ref "J560") (pin "1") (pinfunction "1_1") (pintype "bidirectional"))
    )
    (net (code "73") (name "/PFORCE_N8") (class "Default")
      (node (ref "J562") (pin "5") (pinfunction "5_5") (pintype "bidirectional"))
      (node (ref "J566") (pin "1") (pinfunction "1_1") (pintype "bidirectional"))
    )
    (net (code "74") (name "/PFORCE_N9") (class "Default")
      (node (ref "J562") (pin "9") (pinfunction "9_9") (pintype "bidirectional"))
      (node (ref "J570") (pin "1") (pinfunction "1_1") (pintype "bidirectional"))
    )
    (net (code "75") (name "/PFORCE_N10") (class "Default")
      (node (ref "J571") (pin "5") (pinfunction "5_5") (pintype "bidirectional"))
      (node (ref "J575") (pin "1") (pinfunction "1_1") (pintype "bidirectional"))
    )
    (net (code "76") (name "/PFORCE_N11") (class "Default")
      (node (ref "J571") (pin "9") (pinfunction "9_9") (pintype "bidirectional"))
      (node (ref "J579") (pin "1") (pinfunction "1_1") (pintype "bidirectional"))
    )
    (net (code "77") (name "/PFORCE_N12") (class "Default")
      (node (ref "J580") (pin "5") (pinfunction "5_5") (pintype "bidirectional"))
      (node (ref "J584") (pin "1") (pinfunction "1_1") (pintype "bidirectional"))
    )
    (net (code "78") (name "/PFORCE_N13") (class "Default")
      (node (ref "J580") (pin "9") (pinfunction "9_9") (pintype "bidirectional"))
      (node (ref "J588") (pin "1") (pinfunction "1_1") (pintype "bidirectional"))
    )
    (net (code "79") (name "/PFORCE_N14") (class "Default")
      (node (ref "J589") (pin "5") (pinfunction "5_5") (pintype "bidirectional"))
      (node (ref "J593") (pin "1") (pinfunction "1_1") (pintype "bidirectional"))
    )
    (net (code "80") (name "/PFORCE_N15") (class "Default")
      (node (ref "J589") (pin "9") (pinfunction "9_9") (pintype "bidirectional"))
      (node (ref "J597") (pin "1") (pinfunction "1_1") (pintype "bidirectional"))
    )
    (net (code "81") (name "/PFORCE_P0") (class "Default")
      (node (ref "J525") (pin "2") (pinfunction "2_2") (pintype "bidirectional"))
      (node (ref "J526") (pin "1") (pinfunction "1_1") (pintype "bidirectional"))
    )
    (net (code "82") (name "/PFORCE_P1") (class "Default")
      (node (ref "J525") (pin "6") (pinfunction "6_6") (pintype "bidirectional"))
      (node (ref "J530") (pin "1") (pinfunction "1_1") (pintype "bidirectional"))
    )
    (net (code "83") (name "/PFORCE_P2") (class "Default")
      (node (ref "J534") (pin "2") (pinfunction "2_2") (pintype "bidirectional"))
      (node (ref "J535") (pin "1") (pinfunction "1_1") (pintype "bidirectional"))
    )
    (net (code "84") (name "/PFORCE_P3") (class "Default")
      (node (ref "J534") (pin "6") (pinfunction "6_6") (pintype "bidirectional"))
      (node (ref "J539") (pin "1") (pinfunction "1_1") (pintype "bidirectional"))
    )
    (net (code "85") (name "/PFORCE_P4") (class "Default")
      (node (ref "J543") (pin "2") (pinfunction "2_2") (pintype "bidirectional"))
      (node (ref "J544") (pin "1") (pinfunction "1_1") (pintype "bidirectional"))
    )
    (net (code "86") (name "/PFORCE_P5") (class "Default")
      (node (ref "J543") (pin "6") (pinfunction "6_6") (pintype "bidirectional"))
      (node (ref "J548") (pin "1") (pinfunction "1_1") (pintype "bidirectional"))
    )
    (net (code "87") (name "/PFORCE_P6") (class "Default")
      (node (ref "J552") (pin "2") (pinfunction "2_2") (pintype "bidirectional"))
      (node (ref "J553") (pin "1") (pinfunction "1_1") (pintype "bidirectional"))
    )
    (net (code "88") (name "/PFORCE_P7") (class "Default")
      (node (ref "J552") (pin "6") (pinfunction "6_6") (pintype "bidirectional"))
      (node (ref "J557") (pin "1") (pinfunction "1_1") (pintype "bidirectional"))
    )
    (net (code "89") (name "/PFORCE_P8") (class "Default")
      (node (ref "J562") (pin "2") (pinfunction "2_2") (pintype "bidirectional"))
      (node (ref "J563") (pin "1") (pinfunction "1_1") (pintype "bidirectional"))
    )
    (net (code "90") (name "/PFORCE_P9") (class "Default")
      (node (ref "J562") (pin "6") (pinfunction "6_6") (pintype "bidirectional"))
      (node (ref "J567") (pin "1") (pinfunction "1_1") (pintype "bidirectional"))
    )
    (net (code "91") (name "/PFORCE_P10") (class "Default")
      (node (ref "J571") (pin "2") (pinfunction "2_2") (pintype "bidirectional"))
      (node (ref "J572") (pin "1") (pinfunction "1_1") (pintype "bidirectional"))
    )
    (net (code "92") (name "/PFORCE_P11") (class "Default")
      (node (ref "J571") (pin "6") (pinfunction "6_6") (pintype "bidirectional"))
      (node (ref "J576") (pin "1") (pinfunction "1_1") (pintype "bidirectional"))
    )
    (net (code "93") (name "/PFORCE_P12") (class "Default")
      (node (ref "J580") (pin "2") (pinfunction "2_2") (pintype "bidirectional"))
      (node (ref "J581") (pin "1") (pinfunction "1_1") (pintype "bidirectional"))
    )
    (net (code "94") (name "/PFORCE_P13") (class "Default")
      (node (ref "J580") (pin "6") (pinfunction "6_6") (pintype "bidirectional"))
      (node (ref "J585") (pin "1") (pinfunction "1_1") (pintype "bidirectional"))
    )
    (net (code "95") (name "/PFORCE_P14") (class "Default")
      (node (ref "J589") (pin "2") (pinfunction "2_2") (pintype "bidirectional"))
      (node (ref "J590") (pin "1") (pinfunction "1_1") (pintype "bidirectional"))
    )
    (net (code "96") (name "/PFORCE_P15") (class "Default")
      (node (ref "J589") (pin "6") (pinfunction "6_6") (pintype "bidirectional"))
      (node (ref "J594") (pin "1") (pinfunction "1_1") (pintype "bidirectional"))
    )
    (net (code "97") (name "/PRTDIN_N0") (class "Default")
      (node (ref "J525") (pin "4") (pinfunction "4_4") (pintype "bidirectional"))
      (node (ref "J528") (pin "1") (pinfunction "1_1") (pintype "bidirectional"))
    )
    (net (code "98") (name "/PRTDIN_N1") (class "Default")
      (node (ref "J525") (pin "8") (pinfunction "8_8") (pintype "bidirectional"))
      (node (ref "J532") (pin "1") (pinfunction "1_1") (pintype "bidirectional"))
    )
    (net (code "99") (name "/PRTDIN_N2") (class "Default")
      (node (ref "J534") (pin "4") (pinfunction "4_4") (pintype "bidirectional"))
      (node (ref "J537") (pin "1") (pinfunction "1_1") (pintype "bidirectional"))
    )
    (net (code "100") (name "/PRTDIN_N3") (class "Default")
      (node (ref "J534") (pin "8") (pinfunction "8_8") (pintype "bidirectional"))
      (node (ref "J541") (pin "1") (pinfunction "1_1") (pintype "bidirectional"))
    )
    (net (code "101") (name "/PRTDIN_N4") (class "Default")
      (node (ref "J543") (pin "4") (pinfunction "4_4") (pintype "bidirectional"))
      (node (ref "J546") (pin "1") (pinfunction "1_1") (pintype "bidirectional"))
    )
    (net (code "102") (name "/PRTDIN_N5") (class "Default")
      (node (ref "J543") (pin "8") (pinfunction "8_8") (pintype "bidirectional"))
      (node (ref "J550") (pin "1") (pinfunction "1_1") (pintype "bidirectional"))
    )
    (net (code "103") (name "/PRTDIN_N6") (class "Default")
      (node (ref "J552") (pin "4") (pinfunction "4_4") (pintype "bidirectional"))
      (node (ref "J555") (pin "1") (pinfunction "1_1") (pintype "bidirectional"))
    )
    (net (code "104") (name "/PRTDIN_N7") (class "Default")
      (node (ref "J552") (pin "8") (pinfunction "8_8") (pintype "bidirectional"))
      (node (ref "J559") (pin "1") (pinfunction "1_1") (pintype "bidirectional"))
    )
    (net (code "105") (name "/PRTDIN_N8") (class "Default")
      (node (ref "J562") (pin "4") (pinfunction "4_4") (pintype "bidirectional"))
      (node (ref "J565") (pin "1") (pinfunction "1_1") (pintype "bidirectional"))
    )
    (net (code "106") (name "/PRTDIN_N9") (class "Default")
      (node (ref "J562") (pin "8") (pinfunction "8_8") (pintype "bidirectional"))
      (node (ref "J569") (pin "1") (pinfunction "1_1") (pintype "bidirectional"))
    )
    (net (code "107") (name "/PRTDIN_N10") (class "Default")
      (node (ref "J571") (pin "4") (pinfunction "4_4") (pintype "bidirectional"))
      (node (ref "J574") (pin "1") (pinfunction "1_1") (pintype "bidirectional"))
    )
    (net (code "108") (name "/PRTDIN_N11") (class "Default")
      (node (ref "J571") (pin "8") (pinfunction "8_8") (pintype "bidirectional"))
      (node (ref "J578") (pin "1") (pinfunction "1_1") (pintype "bidirectional"))
    )
    (net (code "109") (name "/PRTDIN_N12") (class "Default")
      (node (ref "J580") (pin "4") (pinfunction "4_4") (pintype "bidirectional"))
      (node (ref "J583") (pin "1") (pinfunction "1_1") (pintype "bidirectional"))
    )
    (net (code "110") (name "/PRTDIN_N13") (class "Default")
      (node (ref "J580") (pin "8") (pinfunction "8_8") (pintype "bidirectional"))
      (node (ref "J587") (pin "1") (pinfunction "1_1") (pintype "bidirectional"))
    )
    (net (code "111") (name "/PRTDIN_N14") (class "Default")
      (node (ref "J589") (pin "4") (pinfunction "4_4") (pintype "bidirectional"))
      (node (ref "J592") (pin "1") (pinfunction "1_1") (pintype "bidirectional"))
    )
    (net (code "112") (name "/PRTDIN_N15") (class "Default")
      (node (ref "J589") (pin "8") (pinfunction "8_8") (pintype "bidirectional"))
      (node (ref "J596") (pin "1") (pinfunction "1_1") (pintype "bidirectional"))
    )
    (net (code "113") (name "/PRTDIN_P0") (class "Default")
      (node (ref "J525") (pin "3") (pinfunction "3_3") (pintype "bidirectional"))
      (node (ref "J527") (pin "1") (pinfunction "1_1") (pintype "bidirectional"))
    )
    (net (code "114") (name "/PRTDIN_P1") (class "Default")
      (node (ref "J525") (pin "7") (pinfunction "7_7") (pintype "bidirectional"))
      (node (ref "J531") (pin "1") (pinfunction "1_1") (pintype "bidirectional"))
    )
    (net (code "115") (name "/PRTDIN_P2") (class "Default")
      (node (ref "J534") (pin "3") (pinfunction "3_3") (pintype "bidirectional"))
      (node (ref "J536") (pin "1") (pinfunction "1_1") (pintype "bidirectional"))
    )
    (net (code "116") (name "/PRTDIN_P3") (class "Default")
      (node (ref "J534") (pin "7") (pinfunction "7_7") (pintype "bidirectional"))
      (node (ref "J540") (pin "1") (pinfunction "1_1") (pintype "bidirectional"))
    )
    (net (code "117") (name "/PRTDIN_P4") (class "Default")
      (node (ref "J543") (pin "3") (pinfunction "3_3") (pintype "bidirectional"))
      (node (ref "J545") (pin "1") (pinfunction "1_1") (pintype "bidirectional"))
    )
    (net (code "118") (name "/PRTDIN_P5") (class "Default")
      (node (ref "J543") (pin "7") (pinfunction "7_7") (pintype "bidirectional"))
      (node (ref "J549") (pin "1") (pinfunction "1_1") (pintype "bidirectional"))
    )
    (net (code "119") (name "/PRTDIN_P6") (class "Default")
      (node (ref "J552") (pin "3") (pinfunction "3_3") (pintype "bidirectional"))
      (node (ref "J554") (pin "1") (pinfunction "1_1") (pintype "bidirectional"))
    )
    (net (code "120") (name "/PRTDIN_P7") (class "Default")
      (node (ref "J552") (pin "7") (pinfunction "7_7") (pintype "bidirectional"))
      (node (ref "J558") (pin "1") (pinfunction "1_1") (pintype "bidirectional"))
    )
    (net (code "121") (name "/PRTDIN_P8") (class "Default")
      (node (ref "J562") (pin "3") (pinfunction "3_3") (pintype "bidirectional"))
      (node (ref "J564") (pin "1") (pinfunction "1_1") (pintype "bidirectional"))
    )
    (net (code "122") (name "/PRTDIN_P9") (class "Default")
      (node (ref "J562") (pin "7") (pinfunction "7_7") (pintype "bidirectional"))
      (node (ref "J568") (pin "1") (pinfunction "1_1") (pintype "bidirectional"))
    )
    (net (code "123") (name "/PRTDIN_P10") (class "Default")
      (node (ref "J571") (pin "3") (pinfunction "3_3") (pintype "bidirectional"))
      (node (ref "J573") (pin "1") (pinfunction "1_1") (pintype "bidirectional"))
    )
    (net (code "124") (name "/PRTDIN_P11") (class "Default")
      (node (ref "J571") (pin "7") (pinfunction "7_7") (pintype "bidirectional"))
      (node (ref "J577") (pin "1") (pinfunction "1_1") (pintype "bidirectional"))
    )
    (net (code "125") (name "/PRTDIN_P12") (class "Default")
      (node (ref "J580") (pin "3") (pinfunction "3_3") (pintype "bidirectional"))
      (node (ref "J582") (pin "1") (pinfunction "1_1") (pintype "bidirectional"))
    )
    (net (code "126") (name "/PRTDIN_P13") (class "Default")
      (node (ref "J580") (pin "7") (pinfunction "7_7") (pintype "bidirectional"))
      (node (ref "J586") (pin "1") (pinfunction "1_1") (pintype "bidirectional"))
    )
    (net (code "127") (name "/PRTDIN_P14") (class "Default")
      (node (ref "J589") (pin "3") (pinfunction "3_3") (pintype "bidirectional"))
      (node (ref "J591") (pin "1") (pinfunction "1_1") (pintype "bidirectional"))
    )
    (net (code "128") (name "/PRTDIN_P15") (class "Default")
      (node (ref "J589") (pin "7") (pinfunction "7_7") (pintype "bidirectional"))
      (node (ref "J595") (pin "1") (pinfunction "1_1") (pintype "bidirectional"))
    )
    (net (code "129") (name "/TFORCE_N0") (class "Default")
      (node (ref "J507") (pin "1") (pinfunction "1_1") (pintype "bidirectional"))
      (node (ref "J514") (pin "5") (pinfunction "5_5") (pintype "bidirectional"))
    )
    (net (code "130") (name "/TFORCE_N1") (class "Default")
      (node (ref "J514") (pin "9") (pinfunction "9_9") (pintype "bidirectional"))
      (node (ref "J515") (pin "1") (pinfunction "1_1") (pintype "bidirectional"))
    )
    (net (code "131") (name "/TFORCE_N2") (class "Default")
      (node (ref "J514") (pin "13") (pinfunction "13_13") (pintype "bidirectional"))
      (node (ref "J516") (pin "1") (pinfunction "1_1") (pintype "bidirectional"))
    )
    (net (code "132") (name "/TFORCE_N3") (class "Default")
      (node (ref "J514") (pin "17") (pinfunction "17_17") (pintype "bidirectional"))
      (node (ref "J518") (pin "1") (pinfunction "1_1") (pintype "bidirectional"))
    )
    (net (code "133") (name "/TFORCE_N4") (class "Default")
      (node (ref "J514") (pin "21") (pinfunction "21_21") (pintype "bidirectional"))
      (node (ref "J519") (pin "1") (pinfunction "1_1") (pintype "bidirectional"))
    )
    (net (code "134") (name "/TFORCE_N5") (class "Default")
      (node (ref "J514") (pin "25") (pinfunction "25_25") (pintype "bidirectional"))
      (node (ref "J520") (pin "1") (pinfunction "1_1") (pintype "bidirectional"))
    )
    (net (code "135") (name "/TFORCE_N6") (class "Default")
      (node (ref "J514") (pin "29") (pinfunction "29_29") (pintype "bidirectional"))
      (node (ref "J523") (pin "1") (pinfunction "1_1") (pintype "bidirectional"))
    )
    (net (code "136") (name "/TFORCE_N7") (class "Default")
      (node (ref "J514") (pin "33") (pinfunction "33_33") (pintype "bidirectional"))
      (node (ref "J524") (pin "1") (pinfunction "1_1") (pintype "bidirectional"))
    )
    (net (code "137") (name "/TFORCE_N8") (class "Default")
      (node (ref "J502") (pin "1") (pinfunction "1_1") (pintype "bidirectional"))
      (node (ref "J514") (pin "39") (pinfunction "39_39") (pintype "bidirectional"))
    )
    (net (code "138") (name "/TFORCE_N9") (class "Default")
      (node (ref "J503") (pin "1") (pinfunction "1_1") (pintype "bidirectional"))
      (node (ref "J514") (pin "43") (pinfunction "43_43") (pintype "bidirectional"))
    )
    (net (code "139") (name "/TFORCE_N10") (class "Default")
      (node (ref "J504") (pin "1") (pinfunction "1_1") (pintype "bidirectional"))
      (node (ref "J514") (pin "47") (pinfunction "47_47") (pintype "bidirectional"))
    )
    (net (code "140") (name "/TFORCE_N11") (class "Default")
      (node (ref "J505") (pin "1") (pinfunction "1_1") (pintype "bidirectional"))
      (node (ref "J514") (pin "51") (pinfunction "51_51") (pintype "bidirectional"))
    )
    (net (code "141") (name "/TFORCE_N12") (class "Default")
      (node (ref "J506") (pin "1") (pinfunction "1_1") (pintype "bidirectional"))
      (node (ref "J514") (pin "55") (pinfunction "55_55") (pintype "bidirectional"))
    )
    (net (code "142") (name "/TFORCE_N13") (class "Default")
      (node (ref "J508") (pin "1") (pinfunction "1_1") (pintype "bidirectional"))
      (node (ref "J514") (pin "59") (pinfunction "59_59") (pintype "bidirectional"))
    )
    (net (code "143") (name "/TFORCE_N14") (class "Default")
      (node (ref "J509") (pin "1") (pinfunction "1_1") (pintype "bidirectional"))
      (node (ref "J514") (pin "63") (pinfunction "63_63") (pintype "bidirectional"))
    )
    (net (code "144") (name "/TFORCE_N15") (class "Default")
      (node (ref "J510") (pin "1") (pinfunction "1_1") (pintype "bidirectional"))
      (node (ref "J514") (pin "67") (pinfunction "67_67") (pintype "bidirectional"))
    )
    (net (code "145") (name "/TFORCE_P0") (class "Default")
      (node (ref "J507") (pin "4") (pinfunction "4_4") (pintype "bidirectional"))
      (node (ref "J514") (pin "2") (pinfunction "2_2") (pintype "bidirectional"))
    )
    (net (code "146") (name "/TFORCE_P1") (class "Default")
      (node (ref "J514") (pin "6") (pinfunction "6_6") (pintype "bidirectional"))
      (node (ref "J515") (pin "4") (pinfunction "4_4") (pintype "bidirectional"))
    )
    (net (code "147") (name "/TFORCE_P2") (class "Default")
      (node (ref "J514") (pin "10") (pinfunction "10_10") (pintype "bidirectional"))
      (node (ref "J516") (pin "4") (pinfunction "4_4") (pintype "bidirectional"))
    )
    (net (code "148") (name "/TFORCE_P3") (class "Default")
      (node (ref "J514") (pin "14") (pinfunction "14_14") (pintype "bidirectional"))
      (node (ref "J518") (pin "4") (pinfunction "4_4") (pintype "bidirectional"))
    )
    (net (code "149") (name "/TFORCE_P4") (class "Default")
      (node (ref "J514") (pin "18") (pinfunction "18_18") (pintype "bidirectional"))
      (node (ref "J519") (pin "4") (pinfunction "4_4") (pintype "bidirectional"))
    )
    (net (code "150") (name "/TFORCE_P5") (class "Default")
      (node (ref "J514") (pin "22") (pinfunction "22_22") (pintype "bidirectional"))
      (node (ref "J520") (pin "4") (pinfunction "4_4") (pintype "bidirectional"))
    )
    (net (code "151") (name "/TFORCE_P6") (class "Default")
      (node (ref "J514") (pin "26") (pinfunction "26_26") (pintype "bidirectional"))
      (node (ref "J523") (pin "4") (pinfunction "4_4") (pintype "bidirectional"))
    )
    (net (code "152") (name "/TFORCE_P7") (class "Default")
      (node (ref "J514") (pin "30") (pinfunction "30_30") (pintype "bidirectional"))
      (node (ref "J524") (pin "4") (pinfunction "4_4") (pintype "bidirectional"))
    )
    (net (code "153") (name "/TFORCE_P8") (class "Default")
      (node (ref "J502") (pin "4") (pinfunction "4_4") (pintype "bidirectional"))
      (node (ref "J514") (pin "36") (pinfunction "36_36") (pintype "bidirectional"))
    )
    (net (code "154") (name "/TFORCE_P9") (class "Default")
      (node (ref "J503") (pin "4") (pinfunction "4_4") (pintype "bidirectional"))
      (node (ref "J514") (pin "40") (pinfunction "40_40") (pintype "bidirectional"))
    )
    (net (code "155") (name "/TFORCE_P10") (class "Default")
      (node (ref "J504") (pin "4") (pinfunction "4_4") (pintype "bidirectional"))
      (node (ref "J514") (pin "44") (pinfunction "44_44") (pintype "bidirectional"))
    )
    (net (code "156") (name "/TFORCE_P11") (class "Default")
      (node (ref "J505") (pin "4") (pinfunction "4_4") (pintype "bidirectional"))
      (node (ref "J514") (pin "48") (pinfunction "48_48") (pintype "bidirectional"))
    )
    (net (code "157") (name "/TFORCE_P12") (class "Default")
      (node (ref "J506") (pin "4") (pinfunction "4_4") (pintype "bidirectional"))
      (node (ref "J514") (pin "52") (pinfunction "52_52") (pintype "bidirectional"))
    )
    (net (code "158") (name "/TFORCE_P13") (class "Default")
      (node (ref "J508") (pin "4") (pinfunction "4_4") (pintype "bidirectional"))
      (node (ref "J514") (pin "56") (pinfunction "56_56") (pintype "bidirectional"))
    )
    (net (code "159") (name "/TFORCE_P14") (class "Default")
      (node (ref "J509") (pin "4") (pinfunction "4_4") (pintype "bidirectional"))
      (node (ref "J514") (pin "60") (pinfunction "60_60") (pintype "bidirectional"))
    )
    (net (code "160") (name "/TFORCE_P15") (class "Default")
      (node (ref "J510") (pin "4") (pinfunction "4_4") (pintype "bidirectional"))
      (node (ref "J514") (pin "64") (pinfunction "64_64") (pintype "bidirectional"))
    )
    (net (code "161") (name "/TRTDIN_N0") (class "Default")
      (node (ref "J507") (pin "2") (pinfunction "2_2") (pintype "bidirectional"))
      (node (ref "J514") (pin "4") (pinfunction "4_4") (pintype "bidirectional"))
    )
    (net (code "162") (name "/TRTDIN_N1") (class "Default")
      (node (ref "J514") (pin "8") (pinfunction "8_8") (pintype "bidirectional"))
      (node (ref "J515") (pin "2") (pinfunction "2_2") (pintype "bidirectional"))
    )
    (net (code "163") (name "/TRTDIN_N2") (class "Default")
      (node (ref "J514") (pin "12") (pinfunction "12_12") (pintype "bidirectional"))
      (node (ref "J516") (pin "2") (pinfunction "2_2") (pintype "bidirectional"))
    )
    (net (code "164") (name "/TRTDIN_N3") (class "Default")
      (node (ref "J514") (pin "16") (pinfunction "16_16") (pintype "bidirectional"))
      (node (ref "J518") (pin "2") (pinfunction "2_2") (pintype "bidirectional"))
    )
    (net (code "165") (name "/TRTDIN_N4") (class "Default")
      (node (ref "J514") (pin "20") (pinfunction "20_20") (pintype "bidirectional"))
      (node (ref "J519") (pin "2") (pinfunction "2_2") (pintype "bidirectional"))
    )
    (net (code "166") (name "/TRTDIN_N5") (class "Default")
      (node (ref "J514") (pin "24") (pinfunction "24_24") (pintype "bidirectional"))
      (node (ref "J520") (pin "2") (pinfunction "2_2") (pintype "bidirectional"))
    )
    (net (code "167") (name "/TRTDIN_N6") (class "Default")
      (node (ref "J514") (pin "28") (pinfunction "28_28") (pintype "bidirectional"))
      (node (ref "J523") (pin "2") (pinfunction "2_2") (pintype "bidirectional"))
    )
    (net (code "168") (name "/TRTDIN_N7") (class "Default")
      (node (ref "J514") (pin "32") (pinfunction "32_32") (pintype "bidirectional"))
      (node (ref "J524") (pin "2") (pinfunction "2_2") (pintype "bidirectional"))
    )
    (net (code "169") (name "/TRTDIN_N8") (class "Default")
      (node (ref "J502") (pin "2") (pinfunction "2_2") (pintype "bidirectional"))
      (node (ref "J514") (pin "38") (pinfunction "38_38") (pintype "bidirectional"))
    )
    (net (code "170") (name "/TRTDIN_N9") (class "Default")
      (node (ref "J503") (pin "2") (pinfunction "2_2") (pintype "bidirectional"))
      (node (ref "J514") (pin "42") (pinfunction "42_42") (pintype "bidirectional"))
    )
    (net (code "171") (name "/TRTDIN_N10") (class "Default")
      (node (ref "J504") (pin "2") (pinfunction "2_2") (pintype "bidirectional"))
      (node (ref "J514") (pin "46") (pinfunction "46_46") (pintype "bidirectional"))
    )
    (net (code "172") (name "/TRTDIN_N11") (class "Default")
      (node (ref "J505") (pin "2") (pinfunction "2_2") (pintype "bidirectional"))
      (node (ref "J514") (pin "50") (pinfunction "50_50") (pintype "bidirectional"))
    )
    (net (code "173") (name "/TRTDIN_N12") (class "Default")
      (node (ref "J506") (pin "2") (pinfunction "2_2") (pintype "bidirectional"))
      (node (ref "J514") (pin "54") (pinfunction "54_54") (pintype "bidirectional"))
    )
    (net (code "174") (name "/TRTDIN_N13") (class "Default")
      (node (ref "J508") (pin "2") (pinfunction "2_2") (pintype "bidirectional"))
      (node (ref "J514") (pin "58") (pinfunction "58_58") (pintype "bidirectional"))
    )
    (net (code "175") (name "/TRTDIN_N14") (class "Default")
      (node (ref "J509") (pin "2") (pinfunction "2_2") (pintype "bidirectional"))
      (node (ref "J514") (pin "62") (pinfunction "62_62") (pintype "bidirectional"))
    )
    (net (code "176") (name "/TRTDIN_N15") (class "Default")
      (node (ref "J510") (pin "2") (pinfunction "2_2") (pintype "bidirectional"))
      (node (ref "J514") (pin "66") (pinfunction "66_66") (pintype "bidirectional"))
    )
    (net (code "177") (name "/TRTDIN_P0") (class "Default")
      (node (ref "J507") (pin "3") (pinfunction "3_3") (pintype "bidirectional"))
      (node (ref "J514") (pin "3") (pinfunction "3_3") (pintype "bidirectional"))
    )
    (net (code "178") (name "/TRTDIN_P1") (class "Default")
      (node (ref "J514") (pin "7") (pinfunction "7_7") (pintype "bidirectional"))
      (node (ref "J515") (pin "3") (pinfunction "3_3") (pintype "bidirectional"))
    )
    (net (code "179") (name "/TRTDIN_P2") (class "Default")
      (node (ref "J514") (pin "11") (pinfunction "11_11") (pintype "bidirectional"))
      (node (ref "J516") (pin "3") (pinfunction "3_3") (pintype "bidirectional"))
    )
    (net (code "180") (name "/TRTDIN_P3") (class "Default")
      (node (ref "J514") (pin "15") (pinfunction "15_15") (pintype "bidirectional"))
      (node (ref "J518") (pin "3") (pinfunction "3_3") (pintype "bidirectional"))
    )
    (net (code "181") (name "/TRTDIN_P4") (class "Default")
      (node (ref "J514") (pin "19") (pinfunction "19_19") (pintype "bidirectional"))
      (node (ref "J519") (pin "3") (pinfunction "3_3") (pintype "bidirectional"))
    )
    (net (code "182") (name "/TRTDIN_P5") (class "Default")
      (node (ref "J514") (pin "23") (pinfunction "23_23") (pintype "bidirectional"))
      (node (ref "J520") (pin "3") (pinfunction "3_3") (pintype "bidirectional"))
    )
    (net (code "183") (name "/TRTDIN_P6") (class "Default")
      (node (ref "J514") (pin "27") (pinfunction "27_27") (pintype "bidirectional"))
      (node (ref "J523") (pin "3") (pinfunction "3_3") (pintype "bidirectional"))
    )
    (net (code "184") (name "/TRTDIN_P7") (class "Default")
      (node (ref "J514") (pin "31") (pinfunction "31_31") (pintype "bidirectional"))
      (node (ref "J524") (pin "3") (pinfunction "3_3") (pintype "bidirectional"))
    )
    (net (code "185") (name "/TRTDIN_P8") (class "Default")
      (node (ref "J502") (pin "3") (pinfunction "3_3") (pintype "bidirectional"))
      (node (ref "J514") (pin "37") (pinfunction "37_37") (pintype "bidirectional"))
    )
    (net (code "186") (name "/TRTDIN_P9") (class "Default")
      (node (ref "J503") (pin "3") (pinfunction "3_3") (pintype "bidirectional"))
      (node (ref "J514") (pin "41") (pinfunction "41_41") (pintype "bidirectional"))
    )
    (net (code "187") (name "/TRTDIN_P10") (class "Default")
      (node (ref "J504") (pin "3") (pinfunction "3_3") (pintype "bidirectional"))
      (node (ref "J514") (pin "45") (pinfunction "45_45") (pintype "bidirectional"))
    )
    (net (code "188") (name "/TRTDIN_P11") (class "Default")
      (node (ref "J505") (pin "3") (pinfunction "3_3") (pintype "bidirectional"))
      (node (ref "J514") (pin "49") (pinfunction "49_49") (pintype "bidirectional"))
    )
    (net (code "189") (name "/TRTDIN_P12") (class "Default")
      (node (ref "J506") (pin "3") (pinfunction "3_3") (pintype "bidirectional"))
      (node (ref "J514") (pin "53") (pinfunction "53_53") (pintype "bidirectional"))
    )
    (net (code "190") (name "/TRTDIN_P13") (class "Default")
      (node (ref "J508") (pin "3") (pinfunction "3_3") (pintype "bidirectional"))
      (node (ref "J514") (pin "57") (pinfunction "57_57") (pintype "bidirectional"))
    )
    (net (code "191") (name "/TRTDIN_P14") (class "Default")
      (node (ref "J509") (pin "3") (pinfunction "3_3") (pintype "bidirectional"))
      (node (ref "J514") (pin "61") (pinfunction "61_61") (pintype "bidirectional"))
    )
    (net (code "192") (name "/TRTDIN_P15") (class "Default")
      (node (ref "J510") (pin "3") (pinfunction "3_3") (pintype "bidirectional"))
      (node (ref "J514") (pin "65") (pinfunction "65_65") (pintype "bidirectional"))
    )
    (net (code "193") (name "GND") (class "Default")
      (node (ref "J500") (pin "1") (pinfunction "1_1") (pintype "bidirectional"))
      (node (ref "J500") (pin "34") (pinfunction "34_34") (pintype "bidirectional"))
      (node (ref "J500") (pin "35") (pinfunction "35_35") (pintype "bidirectional"))
      (node (ref "J500") (pin "68") (pinfunction "68_68") (pintype "bidirectional"))
      (node (ref "J501") (pin "1") (pinfunction "1_1") (pintype "bidirectional"))
      (node (ref "J501") (pin "10") (pinfunction "10_10") (pintype "bidirectional"))
      (node (ref "J511") (pin "1") (pinfunction "1_1") (pintype "bidirectional"))
      (node (ref "J511") (pin "10") (pinfunction "10_10") (pintype "bidirectional"))
      (node (ref "J512") (pin "1") (pinfunction "1_1") (pintype "bidirectional"))
      (node (ref "J512") (pin "10") (pinfunction "10_10") (pintype "bidirectional"))
      (node (ref "J513") (pin "1") (pinfunction "1_1") (pintype "bidirectional"))
      (node (ref "J513") (pin "10") (pinfunction "10_10") (pintype "bidirectional"))
      (node (ref "J514") (pin "1") (pinfunction "1_1") (pintype "bidirectional"))
      (node (ref "J514") (pin "34") (pinfunction "34_34") (pintype "bidirectional"))
      (node (ref "J514") (pin "35") (pinfunction "35_35") (pintype "bidirectional"))
      (node (ref "J514") (pin "68") (pinfunction "68_68") (pintype "bidirectional"))
      (node (ref "J517") (pin "1") (pinfunction "1_1") (pintype "bidirectional"))
      (node (ref "J517") (pin "10") (pinfunction "10_10") (pintype "bidirectional"))
      (node (ref "J521") (pin "1") (pinfunction "1_1") (pintype "bidirectional"))
      (node (ref "J521") (pin "10") (pinfunction "10_10") (pintype "bidirectional"))
      (node (ref "J522") (pin "1") (pinfunction "1_1") (pintype "bidirectional"))
      (node (ref "J522") (pin "10") (pinfunction "10_10") (pintype "bidirectional"))
      (node (ref "J525") (pin "1") (pinfunction "1_1") (pintype "bidirectional"))
      (node (ref "J525") (pin "10") (pinfunction "10_10") (pintype "bidirectional"))
      (node (ref "J534") (pin "1") (pinfunction "1_1") (pintype "bidirectional"))
      (node (ref "J534") (pin "10") (pinfunction "10_10") (pintype "bidirectional"))
      (node (ref "J543") (pin "1") (pinfunction "1_1") (pintype "bidirectional"))
      (node (ref "J543") (pin "10") (pinfunction "10_10") (pintype "bidirectional"))
      (node (ref "J552") (pin "1") (pinfunction "1_1") (pintype "bidirectional"))
      (node (ref "J552") (pin "10") (pinfunction "10_10") (pintype "bidirectional"))
      (node (ref "J561") (pin "1") (pinfunction "1_1") (pintype "bidirectional"))
      (node (ref "J561") (pin "10") (pinfunction "10_10") (pintype "bidirectional"))
      (node (ref "J562") (pin "1") (pinfunction "1_1") (pintype "bidirectional"))
      (node (ref "J562") (pin "10") (pinfunction "10_10") (pintype "bidirectional"))
      (node (ref "J571") (pin "1") (pinfunction "1_1") (pintype "bidirectional"))
      (node (ref "J571") (pin "10") (pinfunction "10_10") (pintype "bidirectional"))
      (node (ref "J580") (pin "1") (pinfunction "1_1") (pintype "bidirectional"))
      (node (ref "J580") (pin "10") (pinfunction "10_10") (pintype "bidirectional"))
      (node (ref "J589") (pin "1") (pinfunction "1_1") (pintype "bidirectional"))
      (node (ref "J589") (pin "10") (pinfunction "10_10") (pintype "bidirectional"))
    )
    (net (code "194") (name "unconnected-(J500-Pad69)") (class "Default")
      (node (ref "J500") (pin "69") (pinfunction "69_69") (pintype "passive"))
    )
    (net (code "195") (name "unconnected-(J500-Pad70)") (class "Default")
      (node (ref "J500") (pin "70") (pinfunction "70_70") (pintype "passive"))
    )
    (net (code "196") (name "unconnected-(J514-Pad69)") (class "Default")
      (node (ref "J514") (pin "69") (pinfunction "69_69") (pintype "passive"))
    )
    (net (code "197") (name "unconnected-(J514-Pad70)") (class "Default")
      (node (ref "J514") (pin "70") (pinfunction "70_70") (pintype "passive"))
    )
  )
)
